# xio.net
KiCad netlist of a schematic drawn in EAGLE
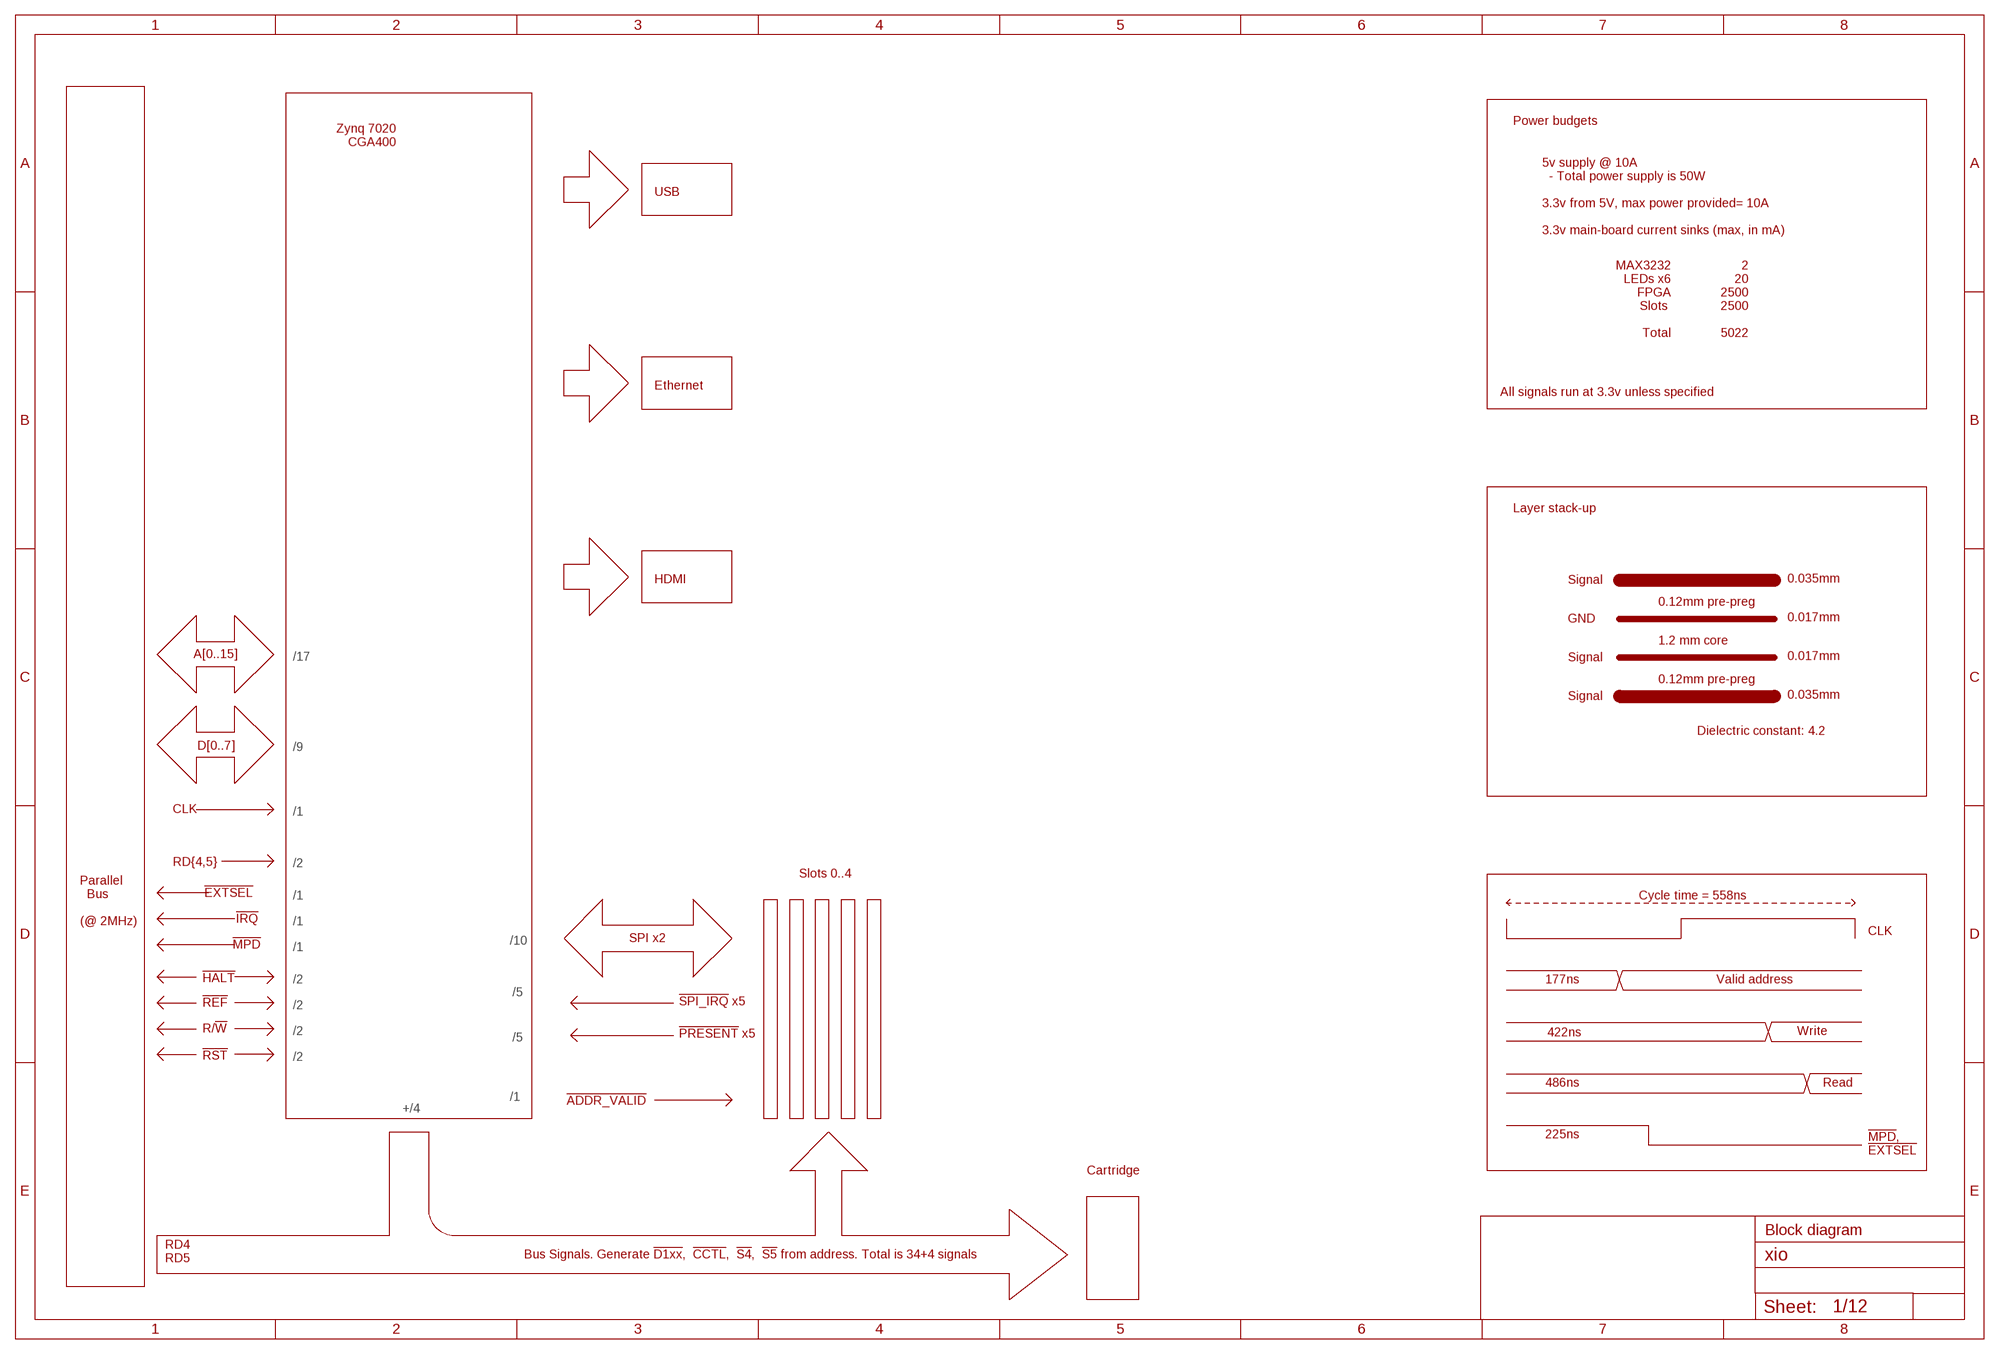
[diagram p0: schematic, sheet 1]
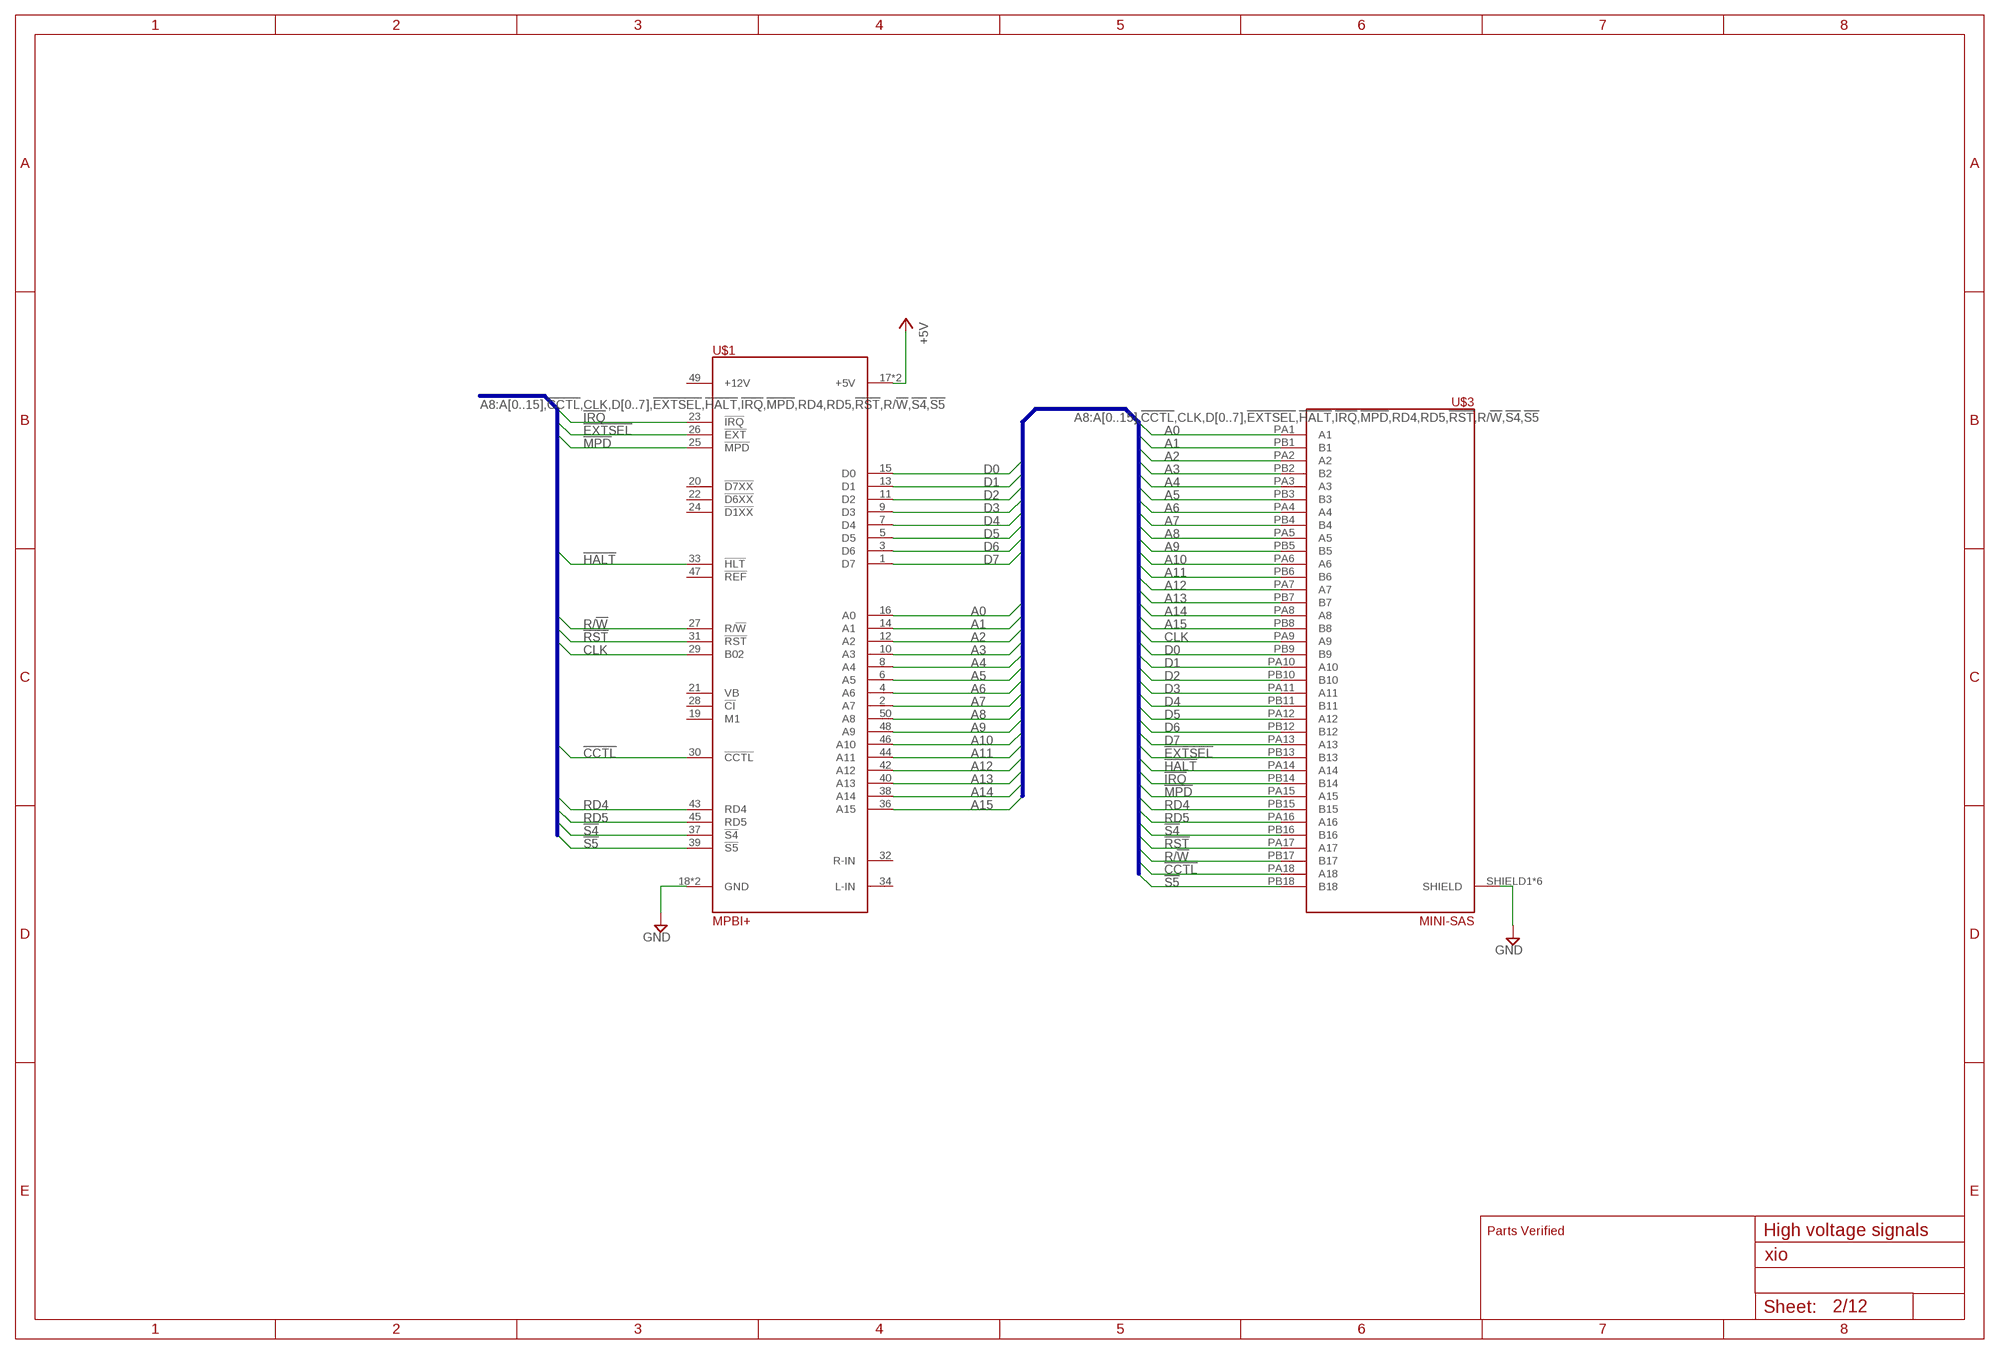
[diagram p1: schematic, sheet 2]
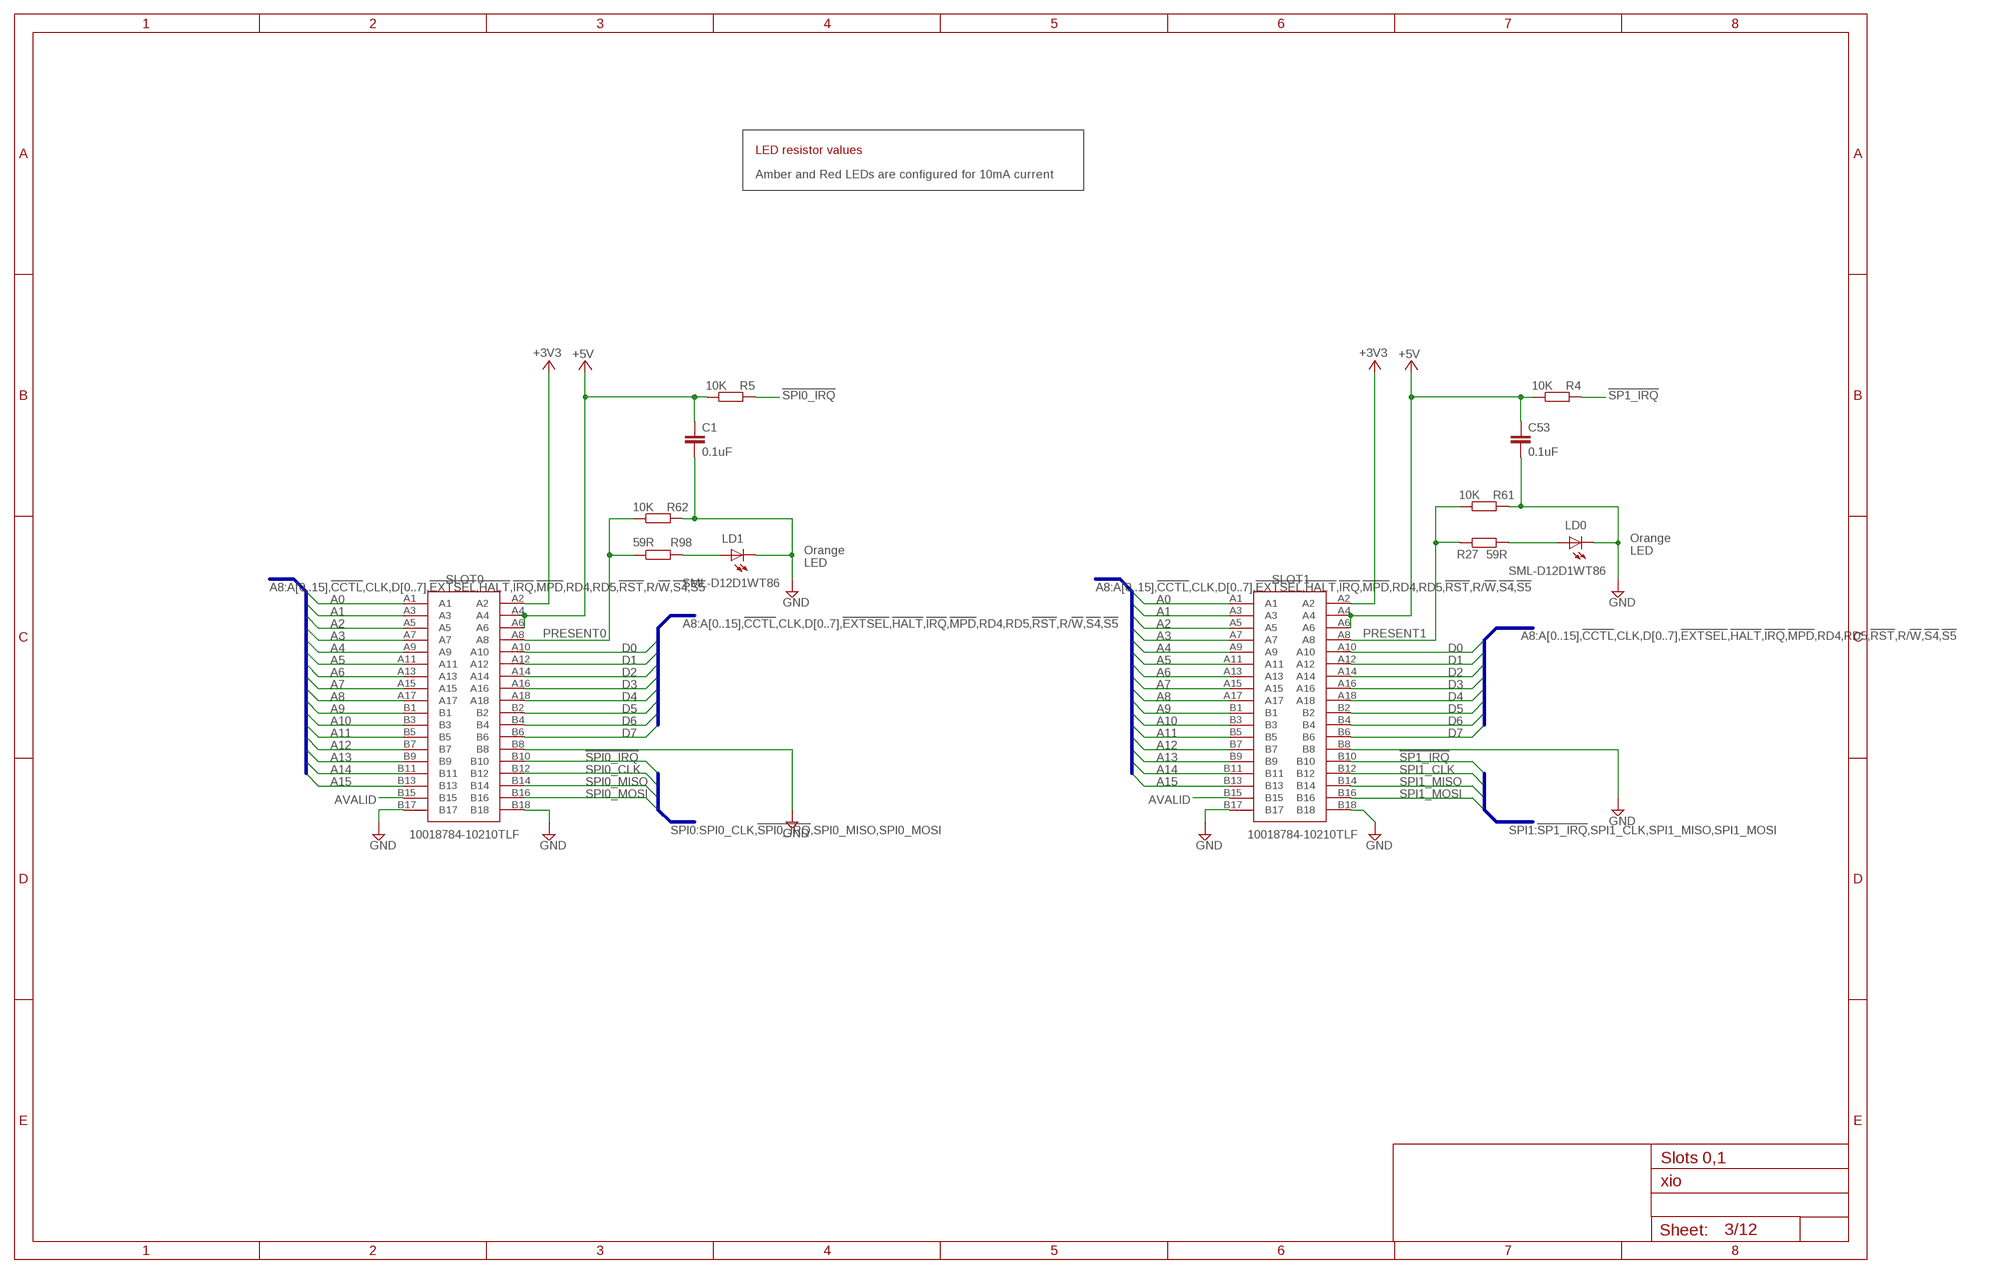
[diagram p2: schematic, sheet 3]
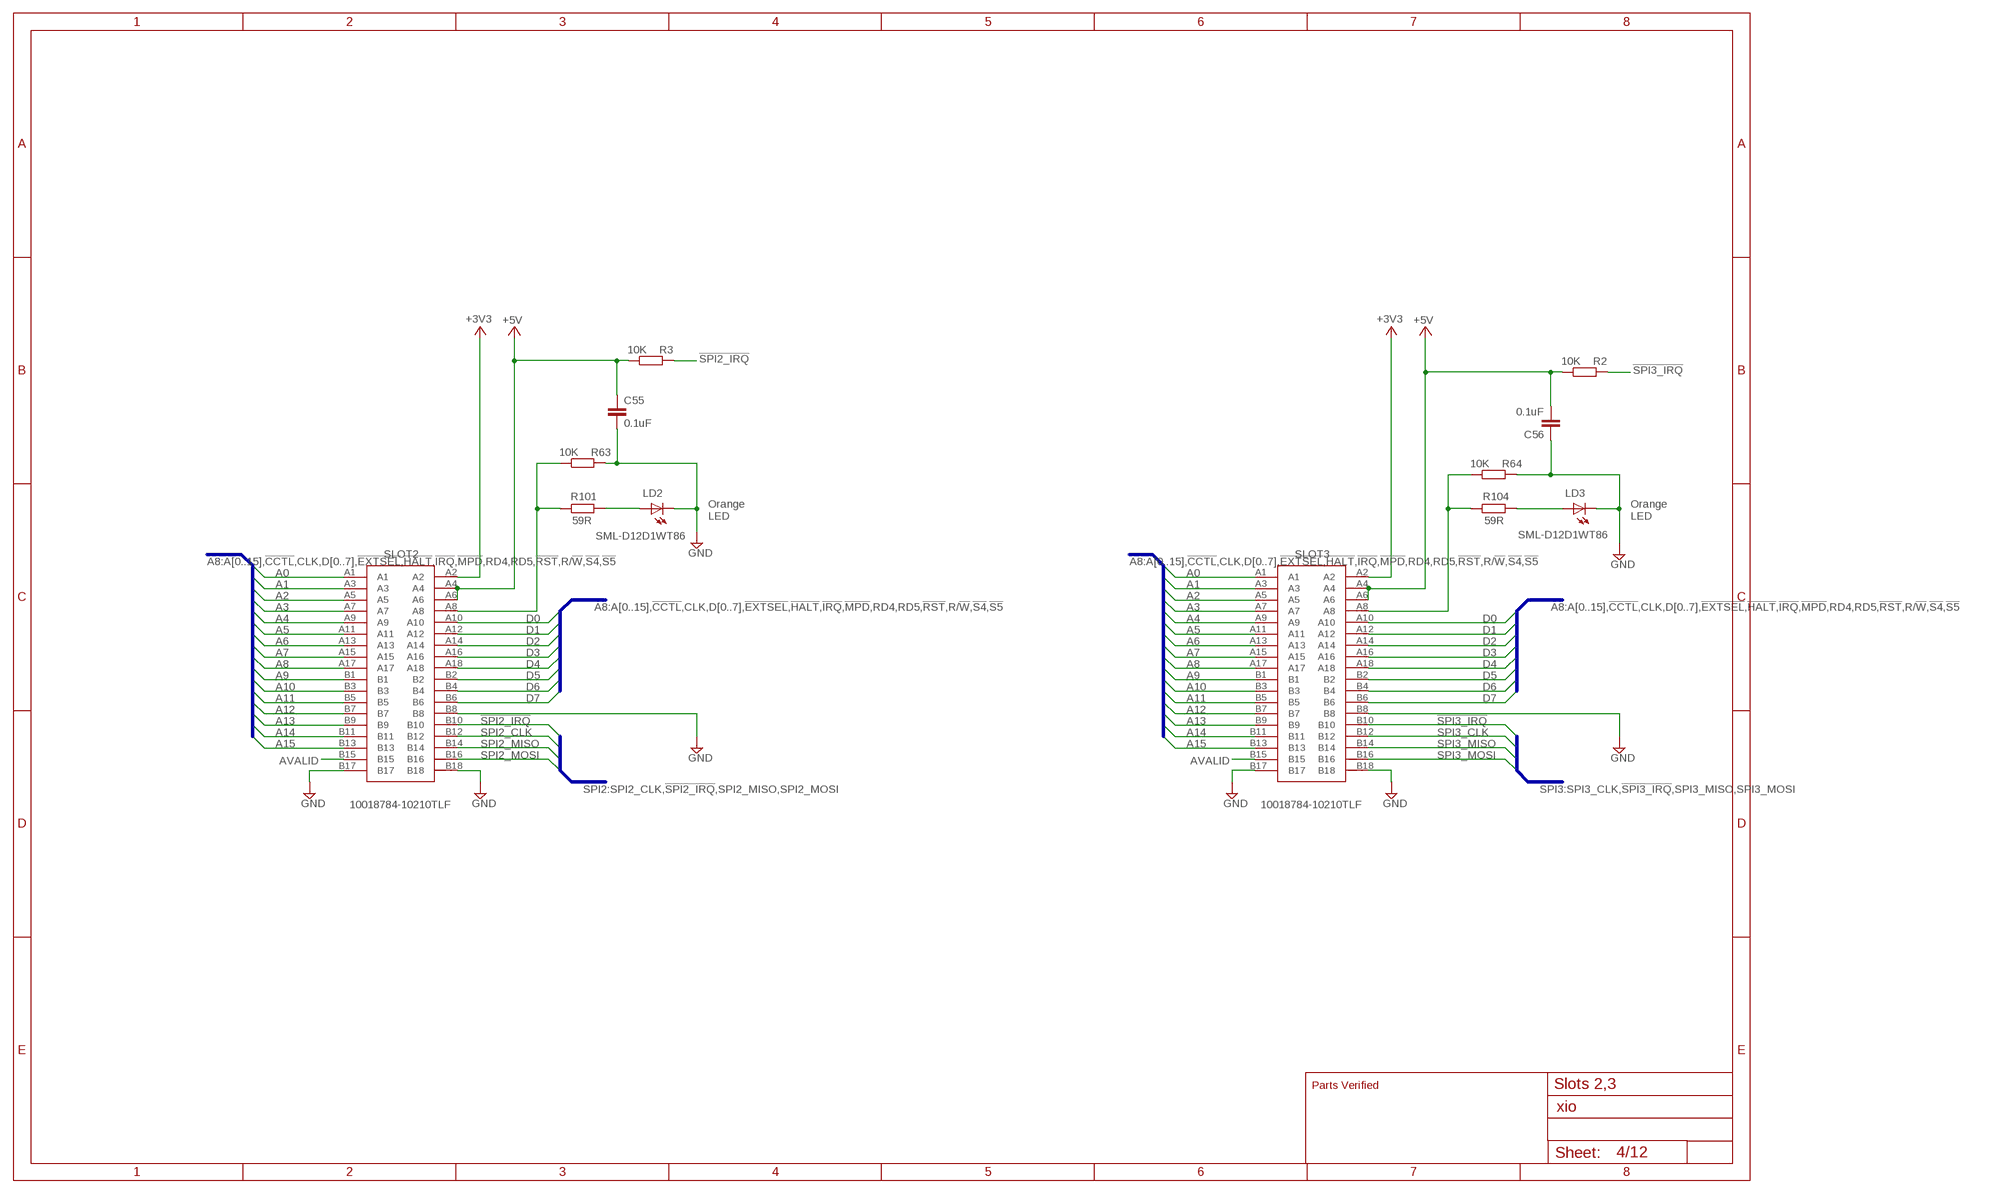
[diagram p3: schematic, sheet 4]
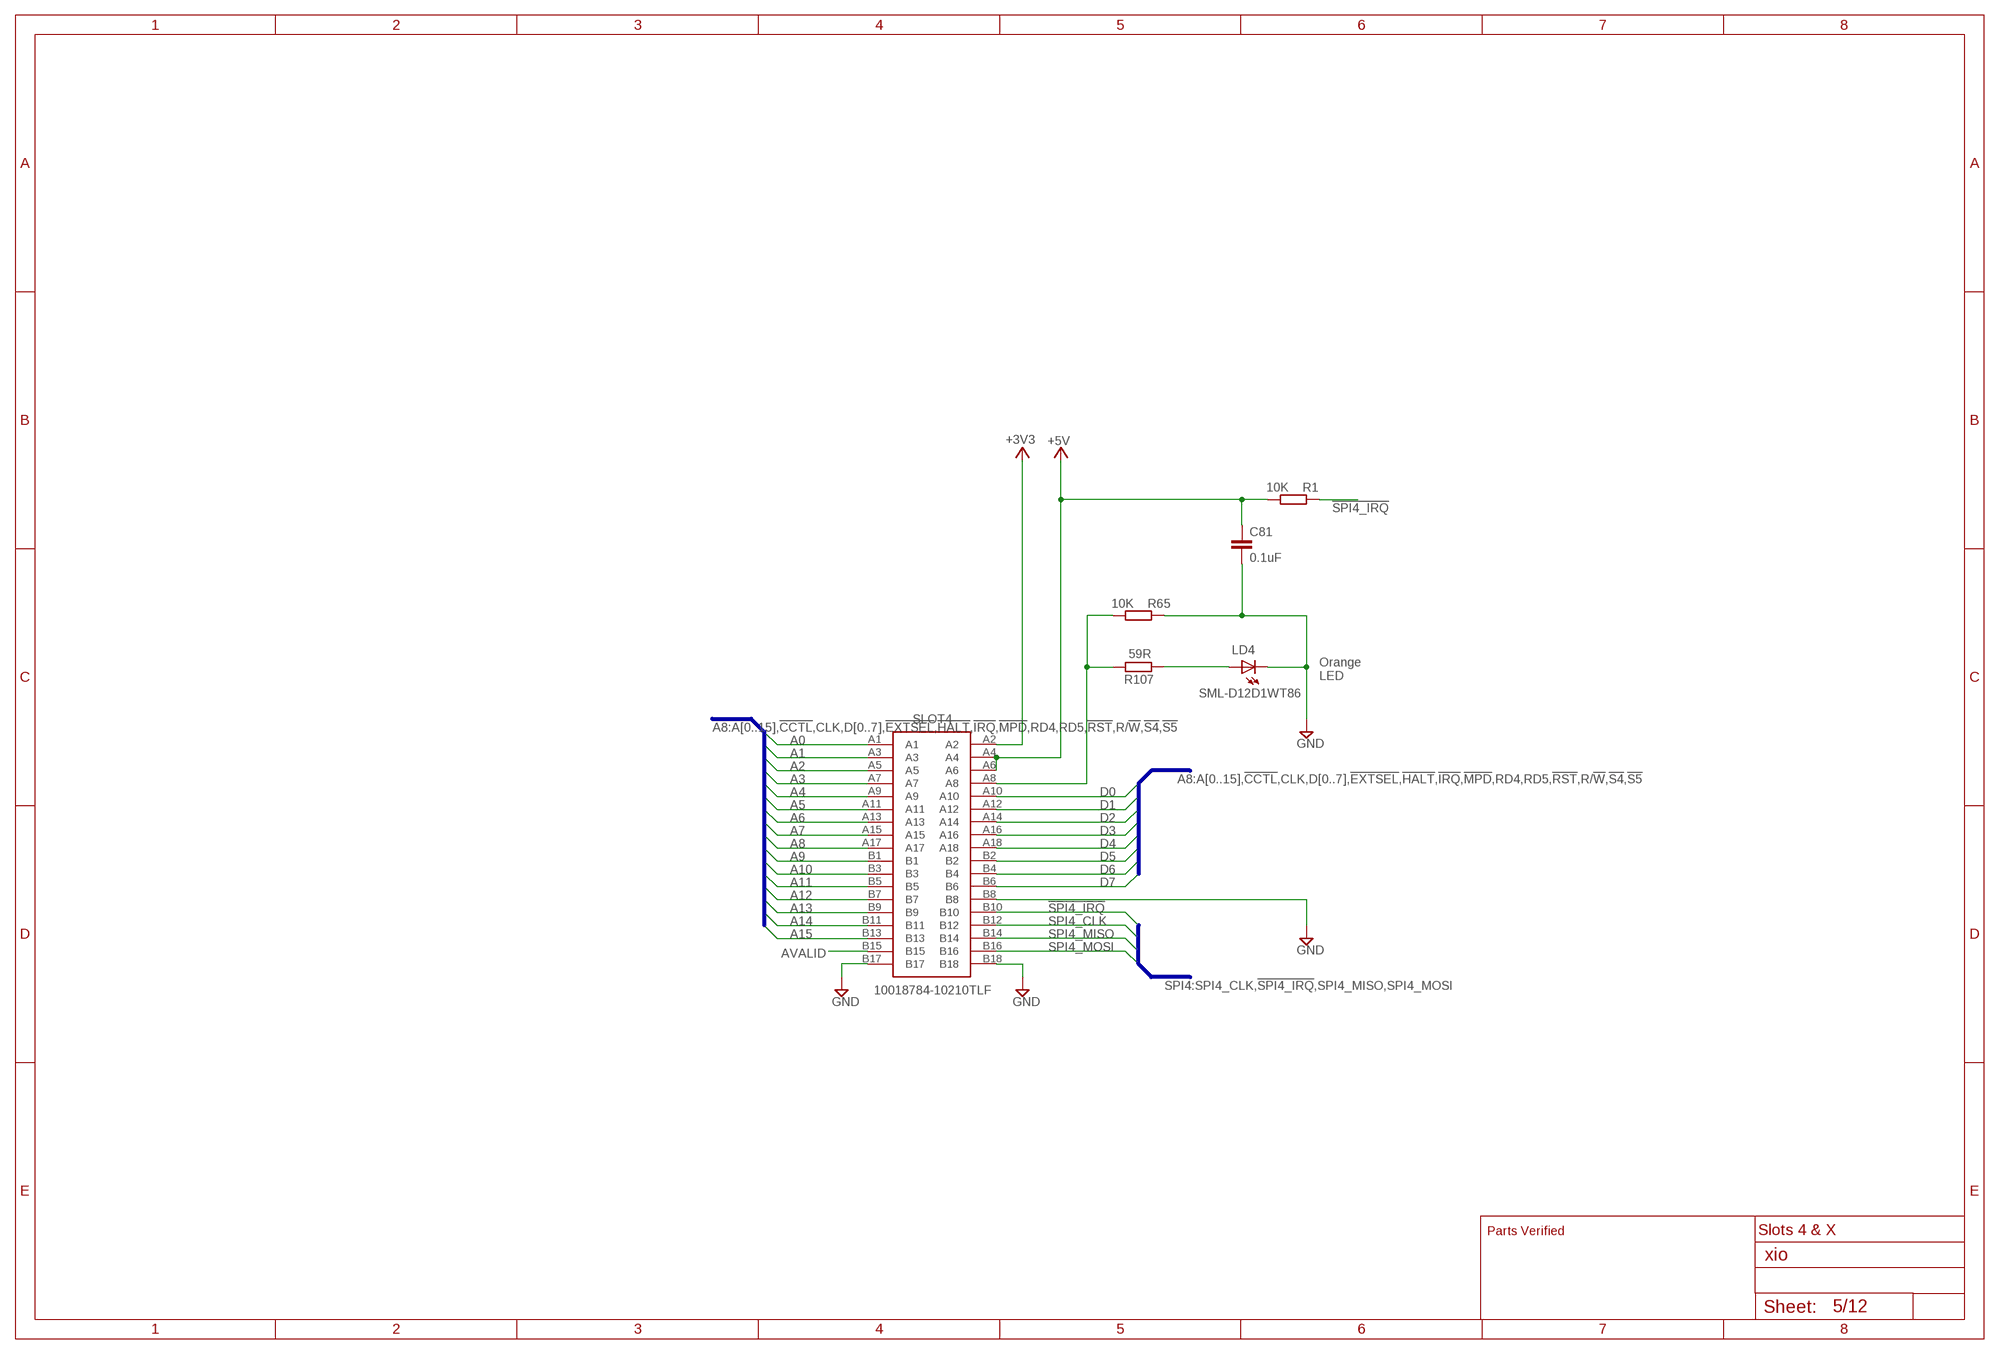
[diagram p4: schematic, sheet 5]
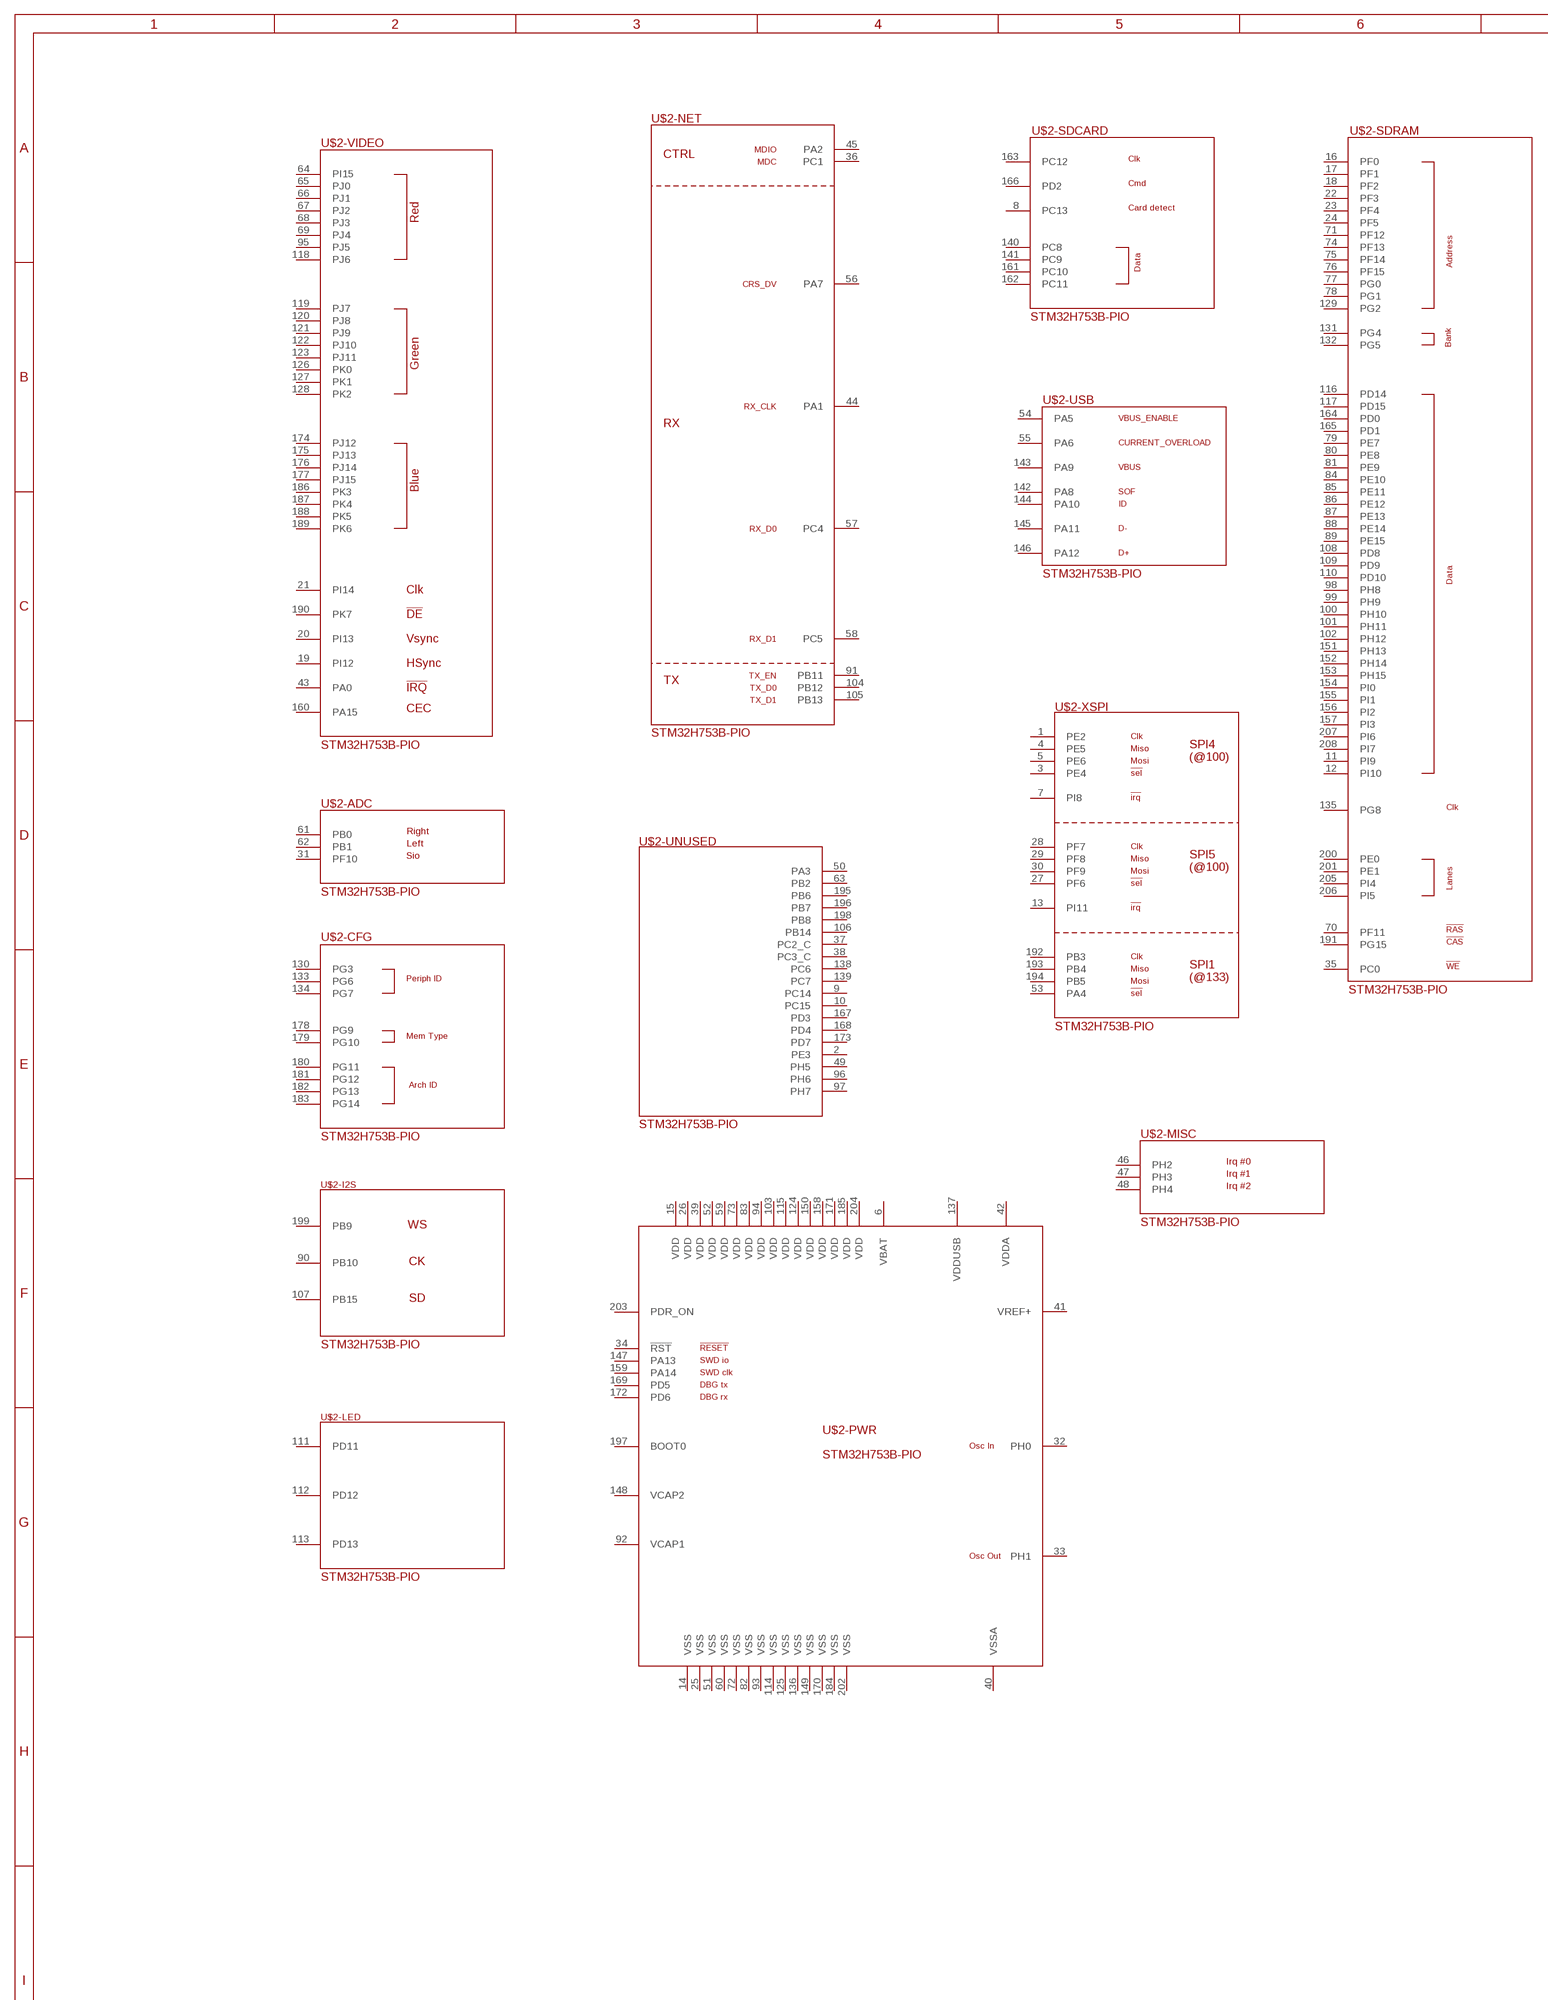
[diagram p5: schematic, sheet 6, part 1 of 2]
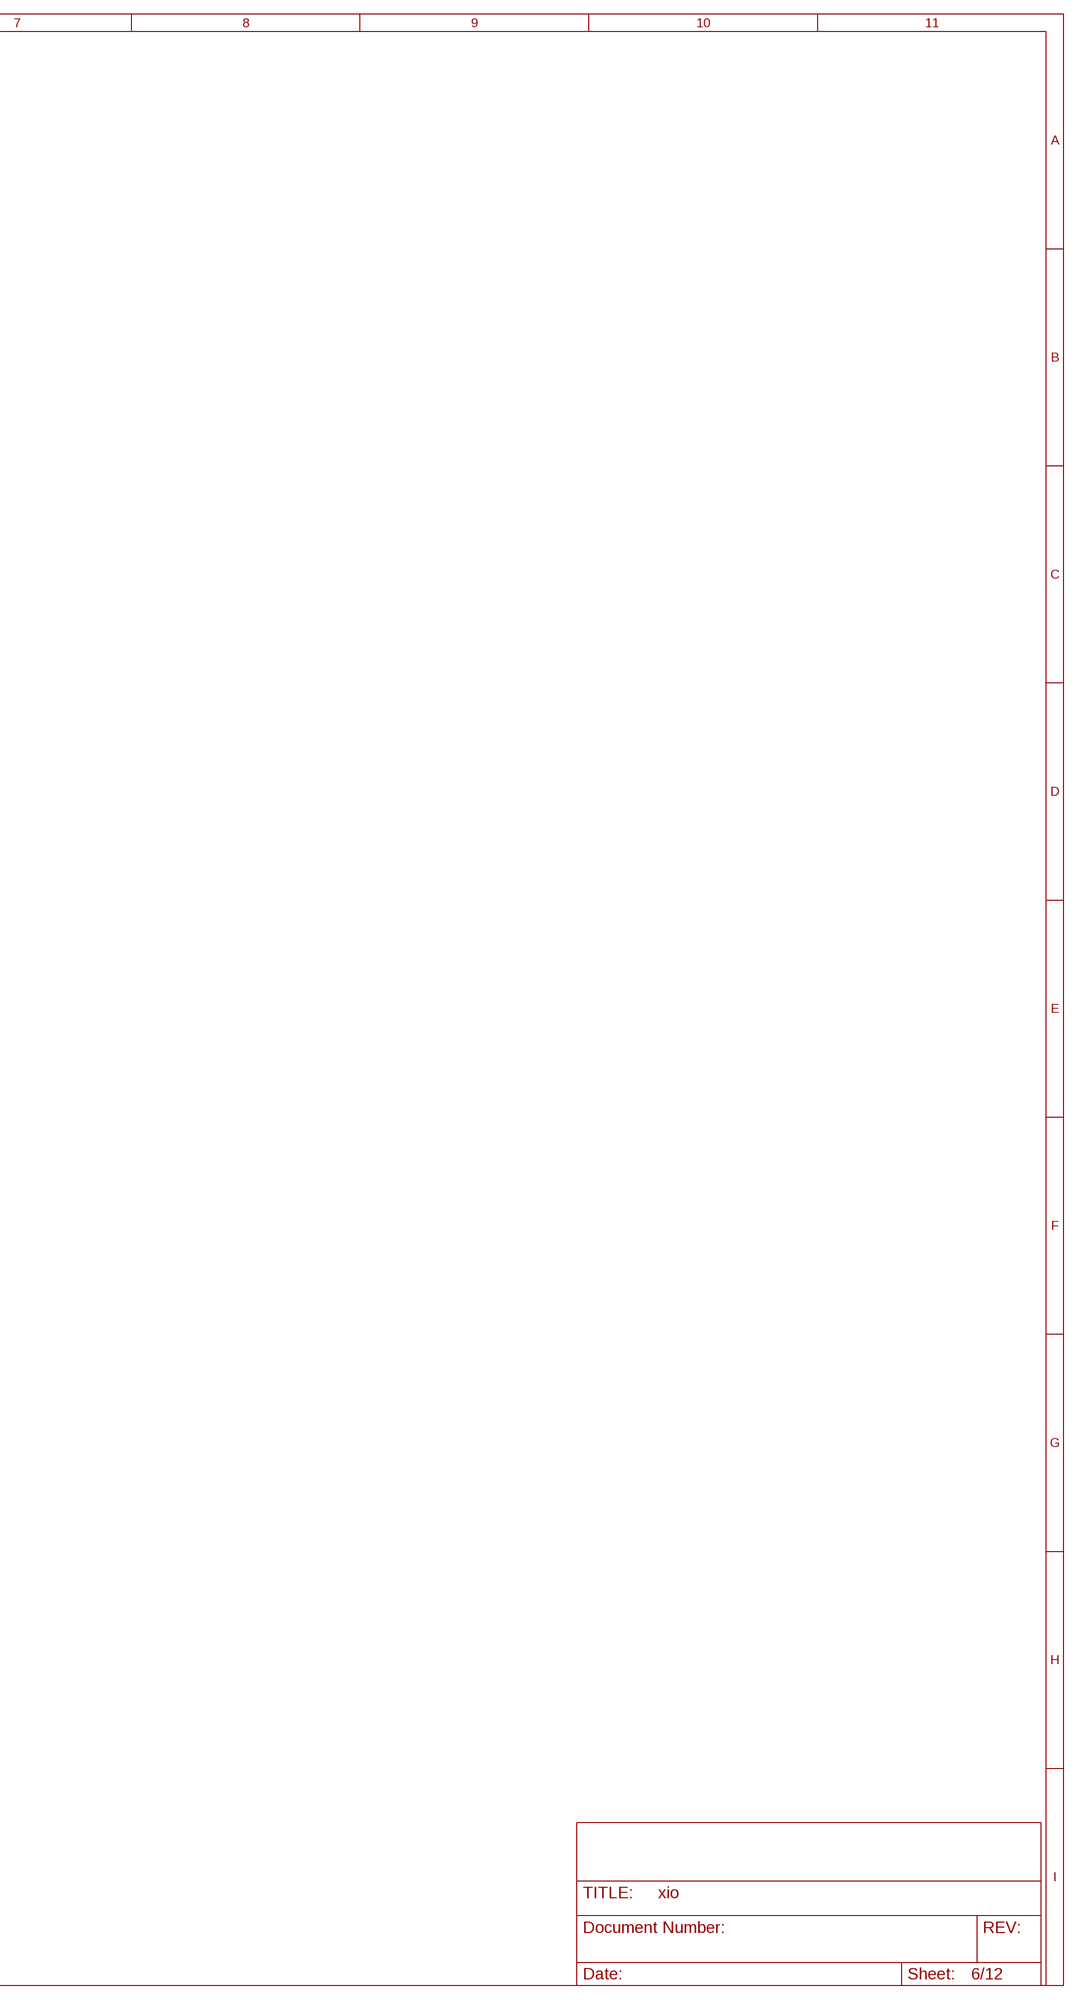
[diagram p6: schematic, sheet 6, part 2 of 2]
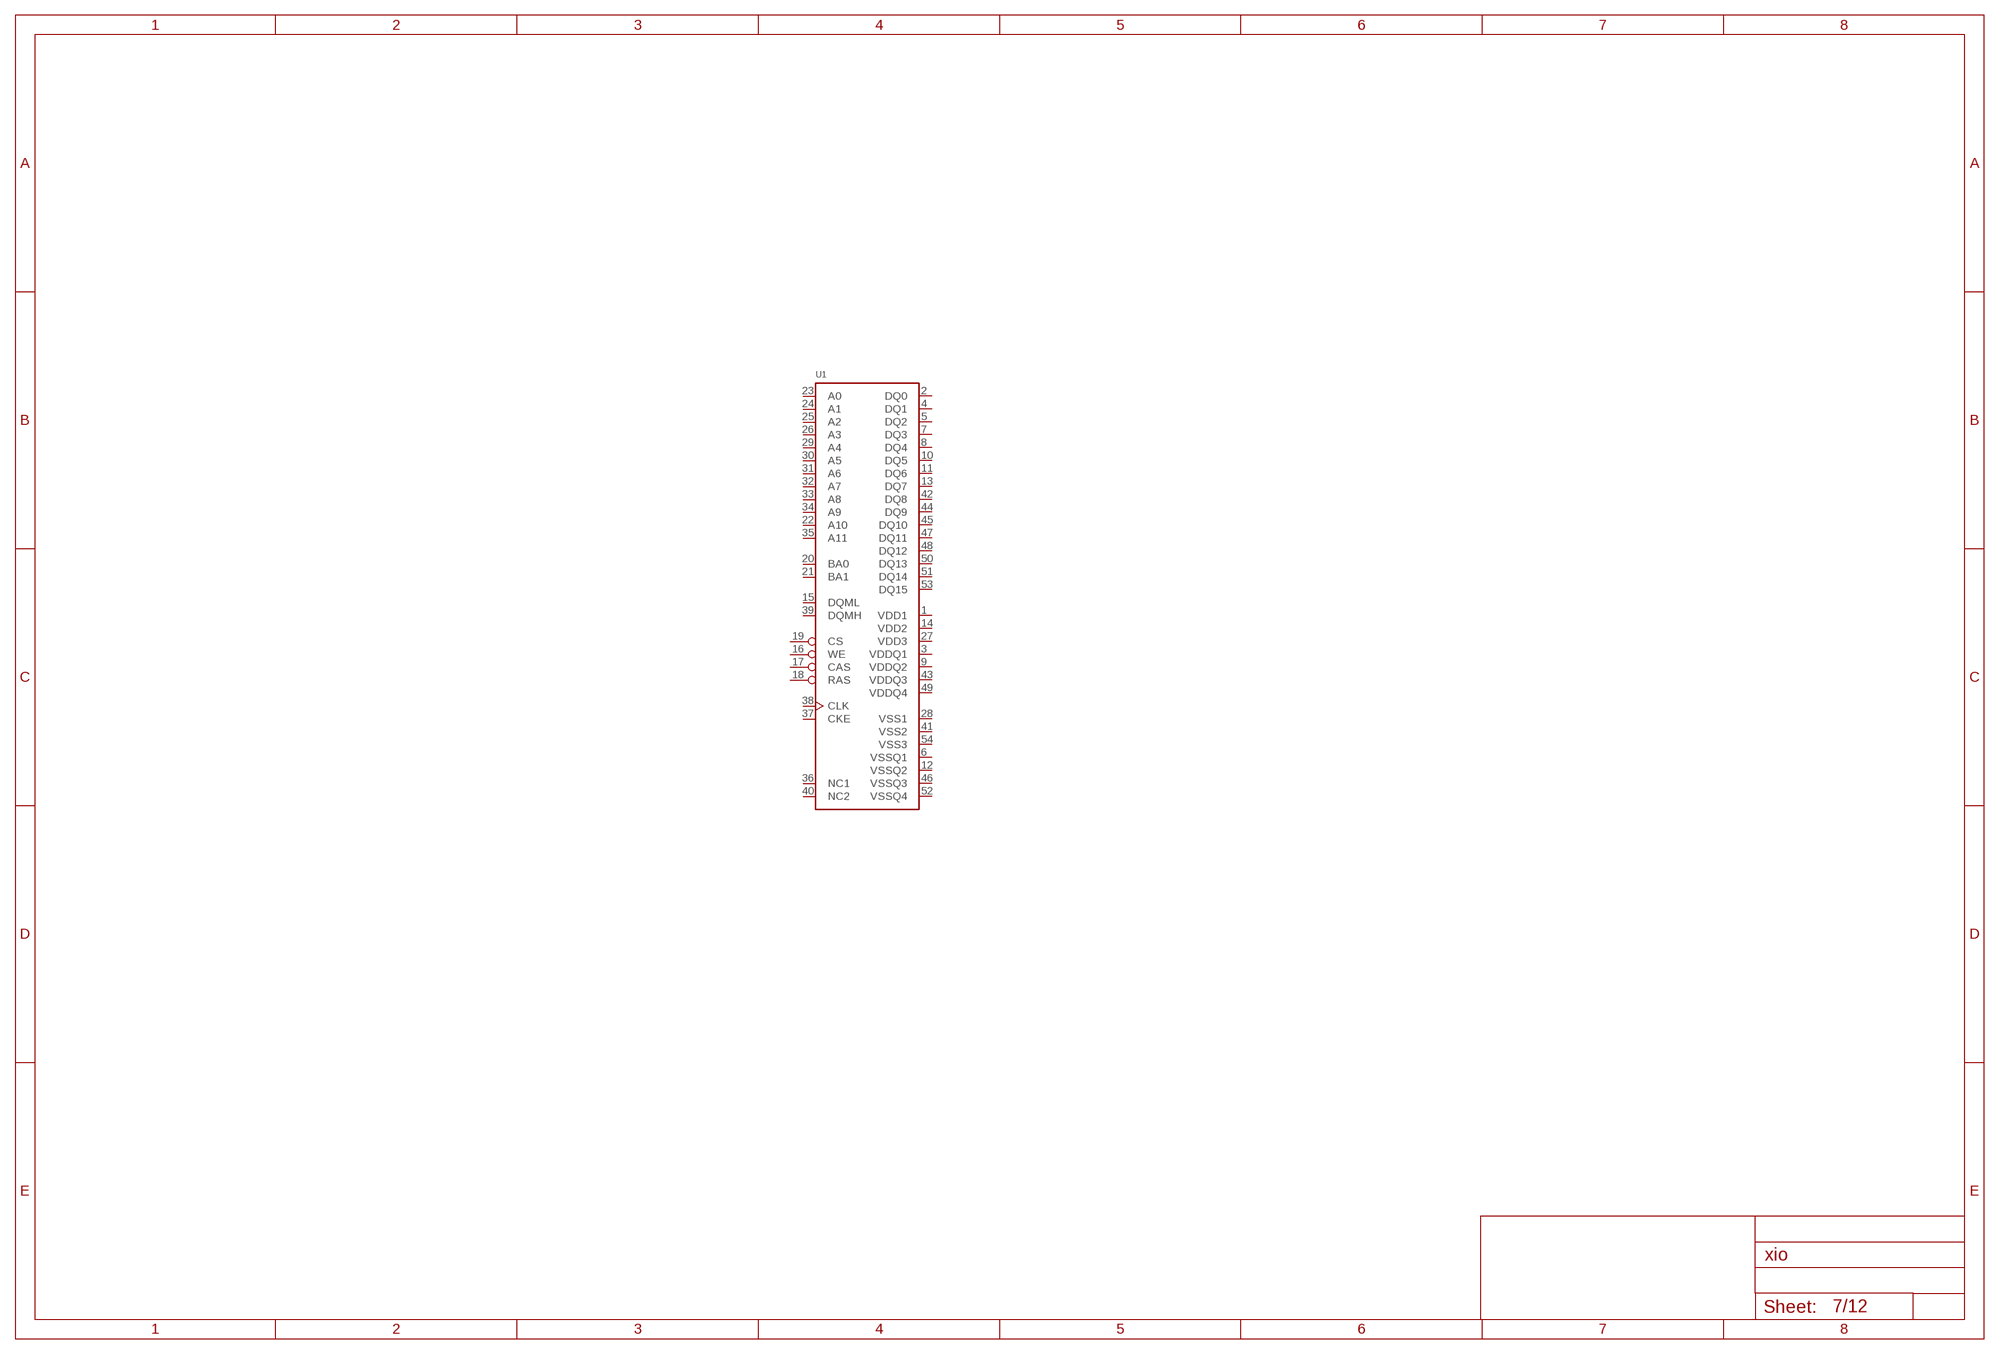
[diagram p7: schematic, sheet 7]
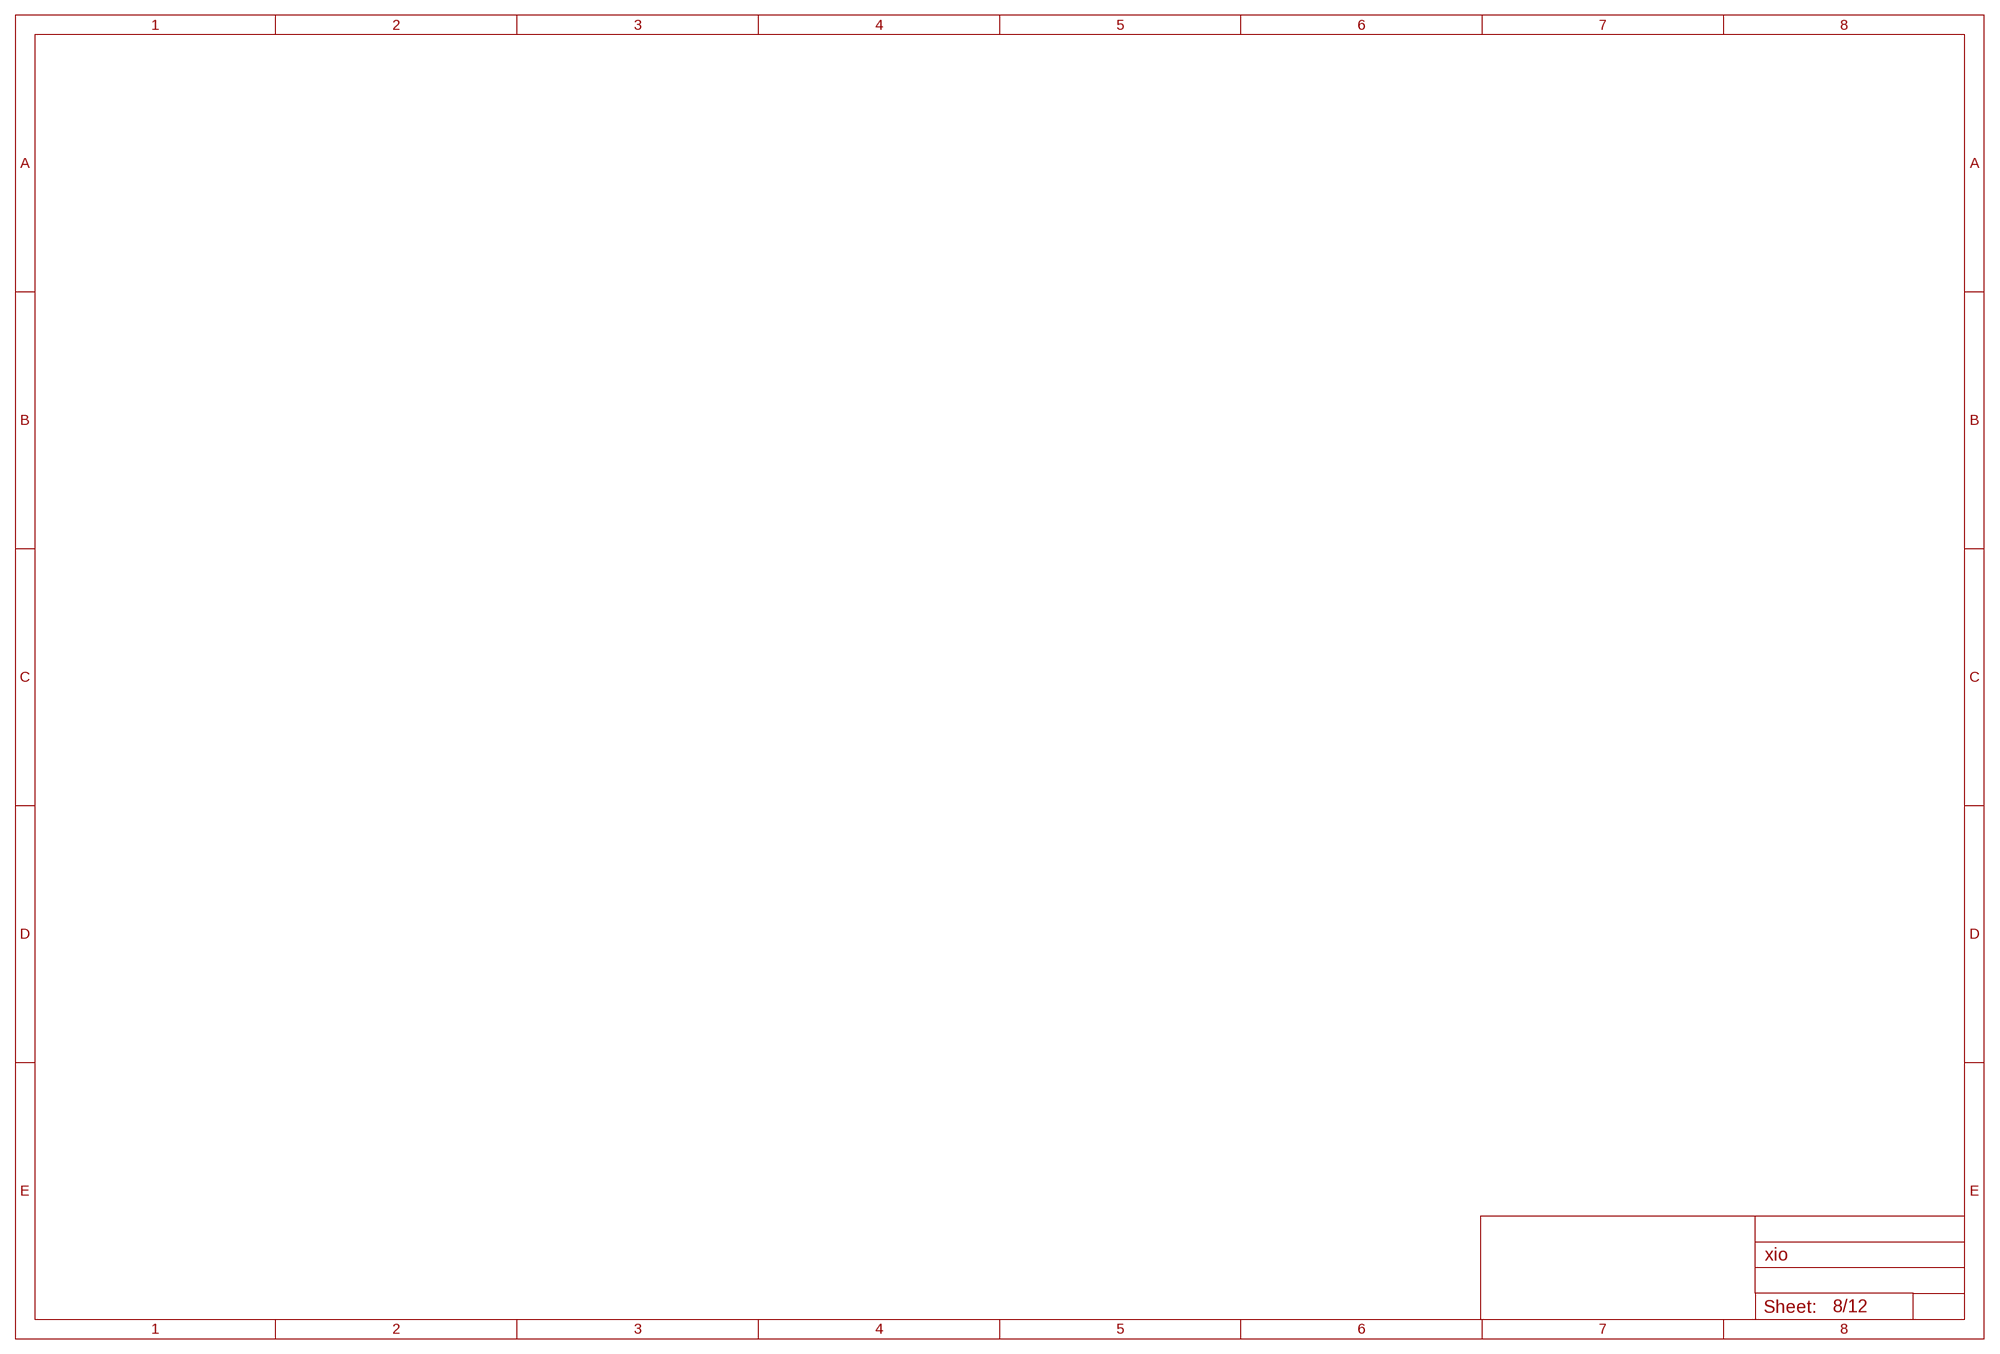
[diagram p8: schematic, sheet 8]
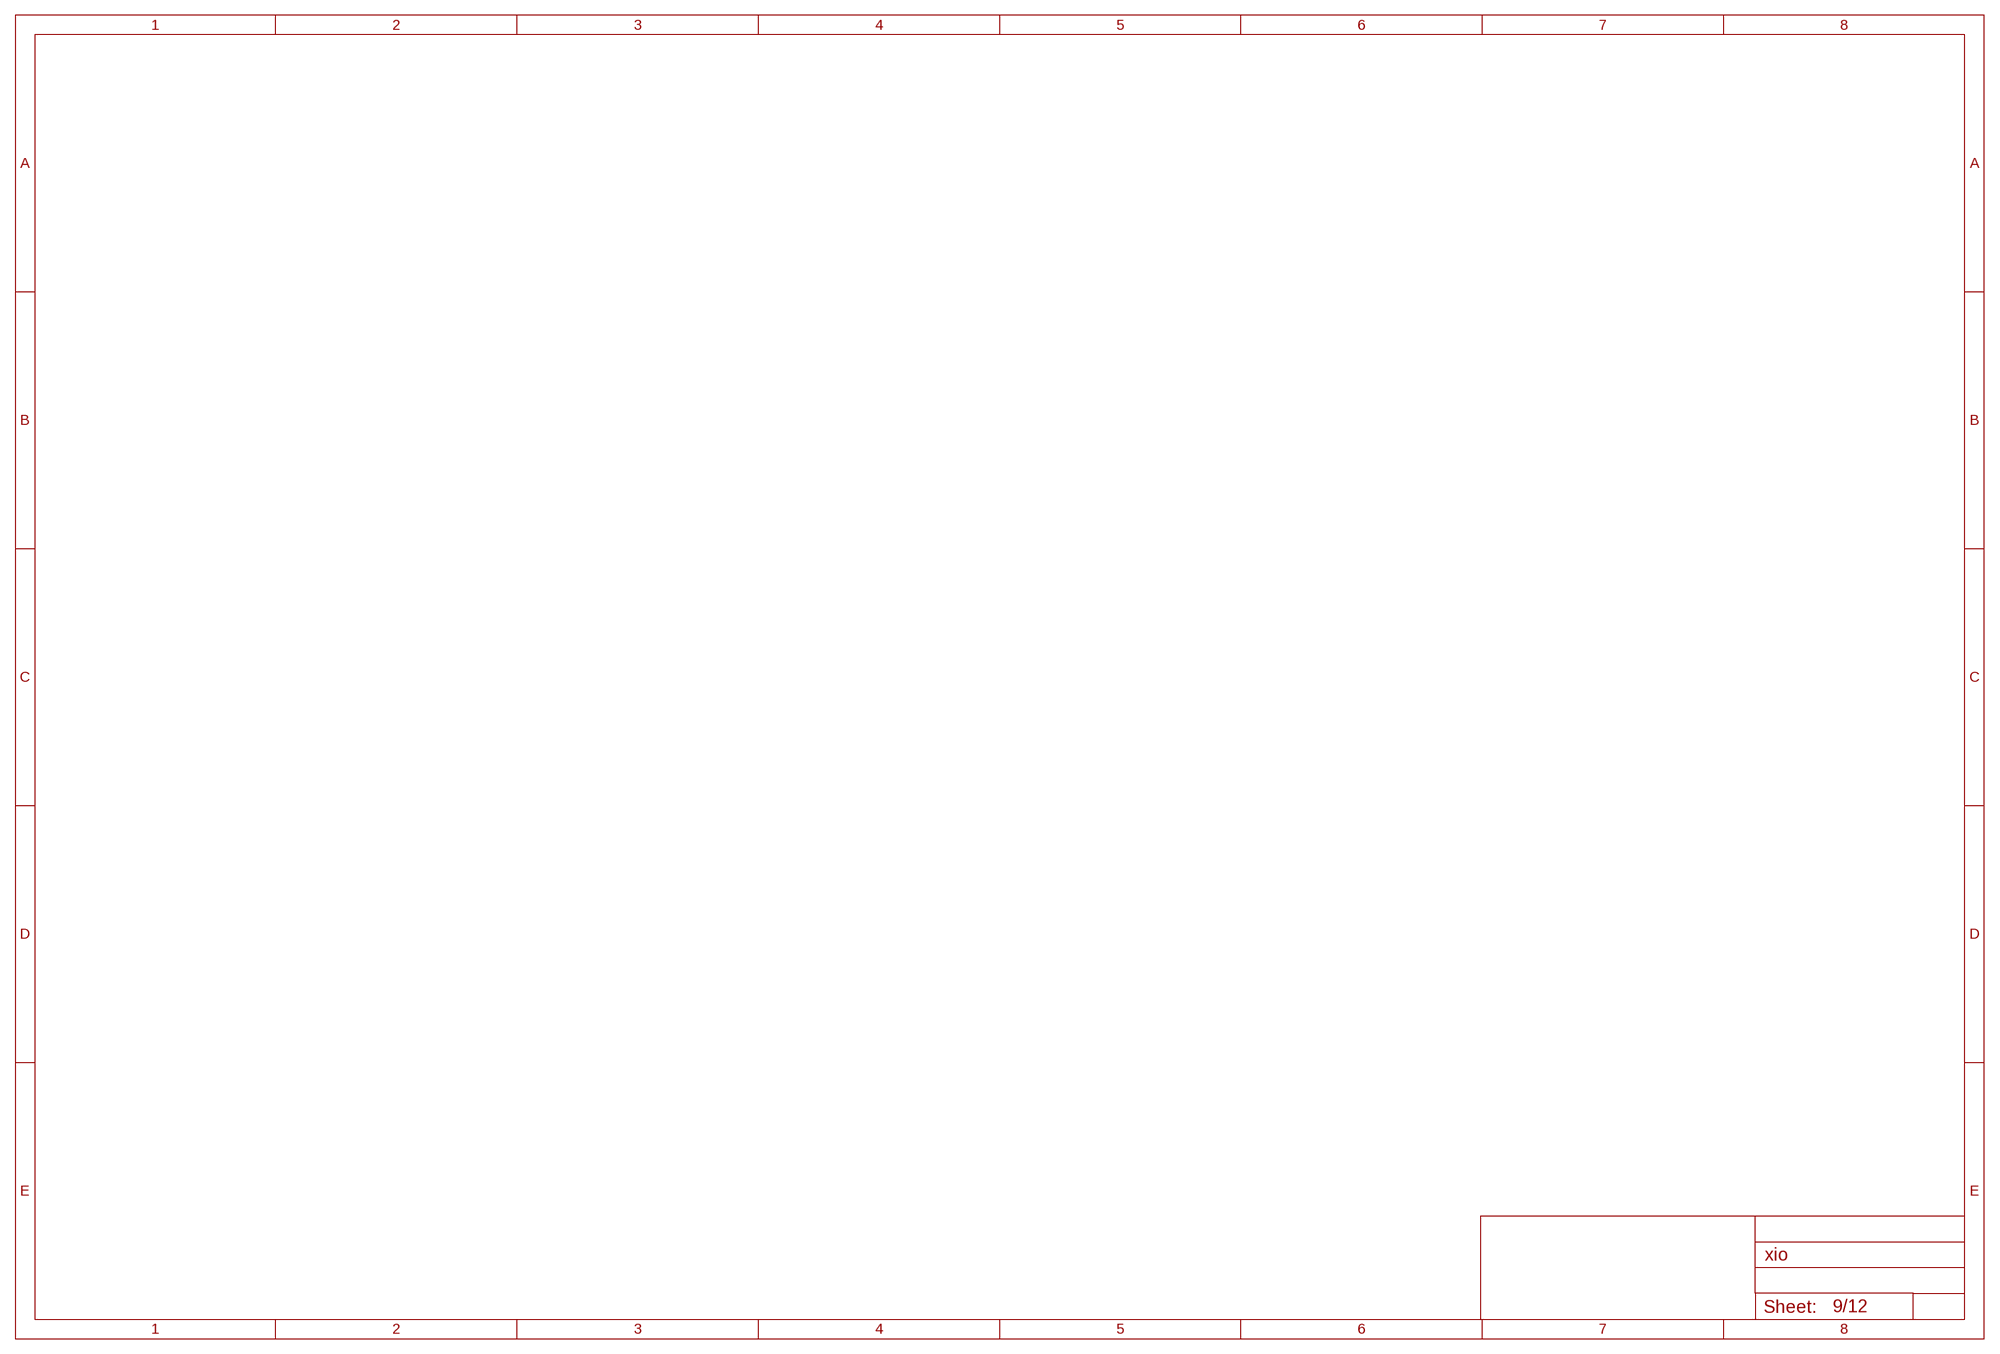
[diagram p9: schematic, sheet 9]
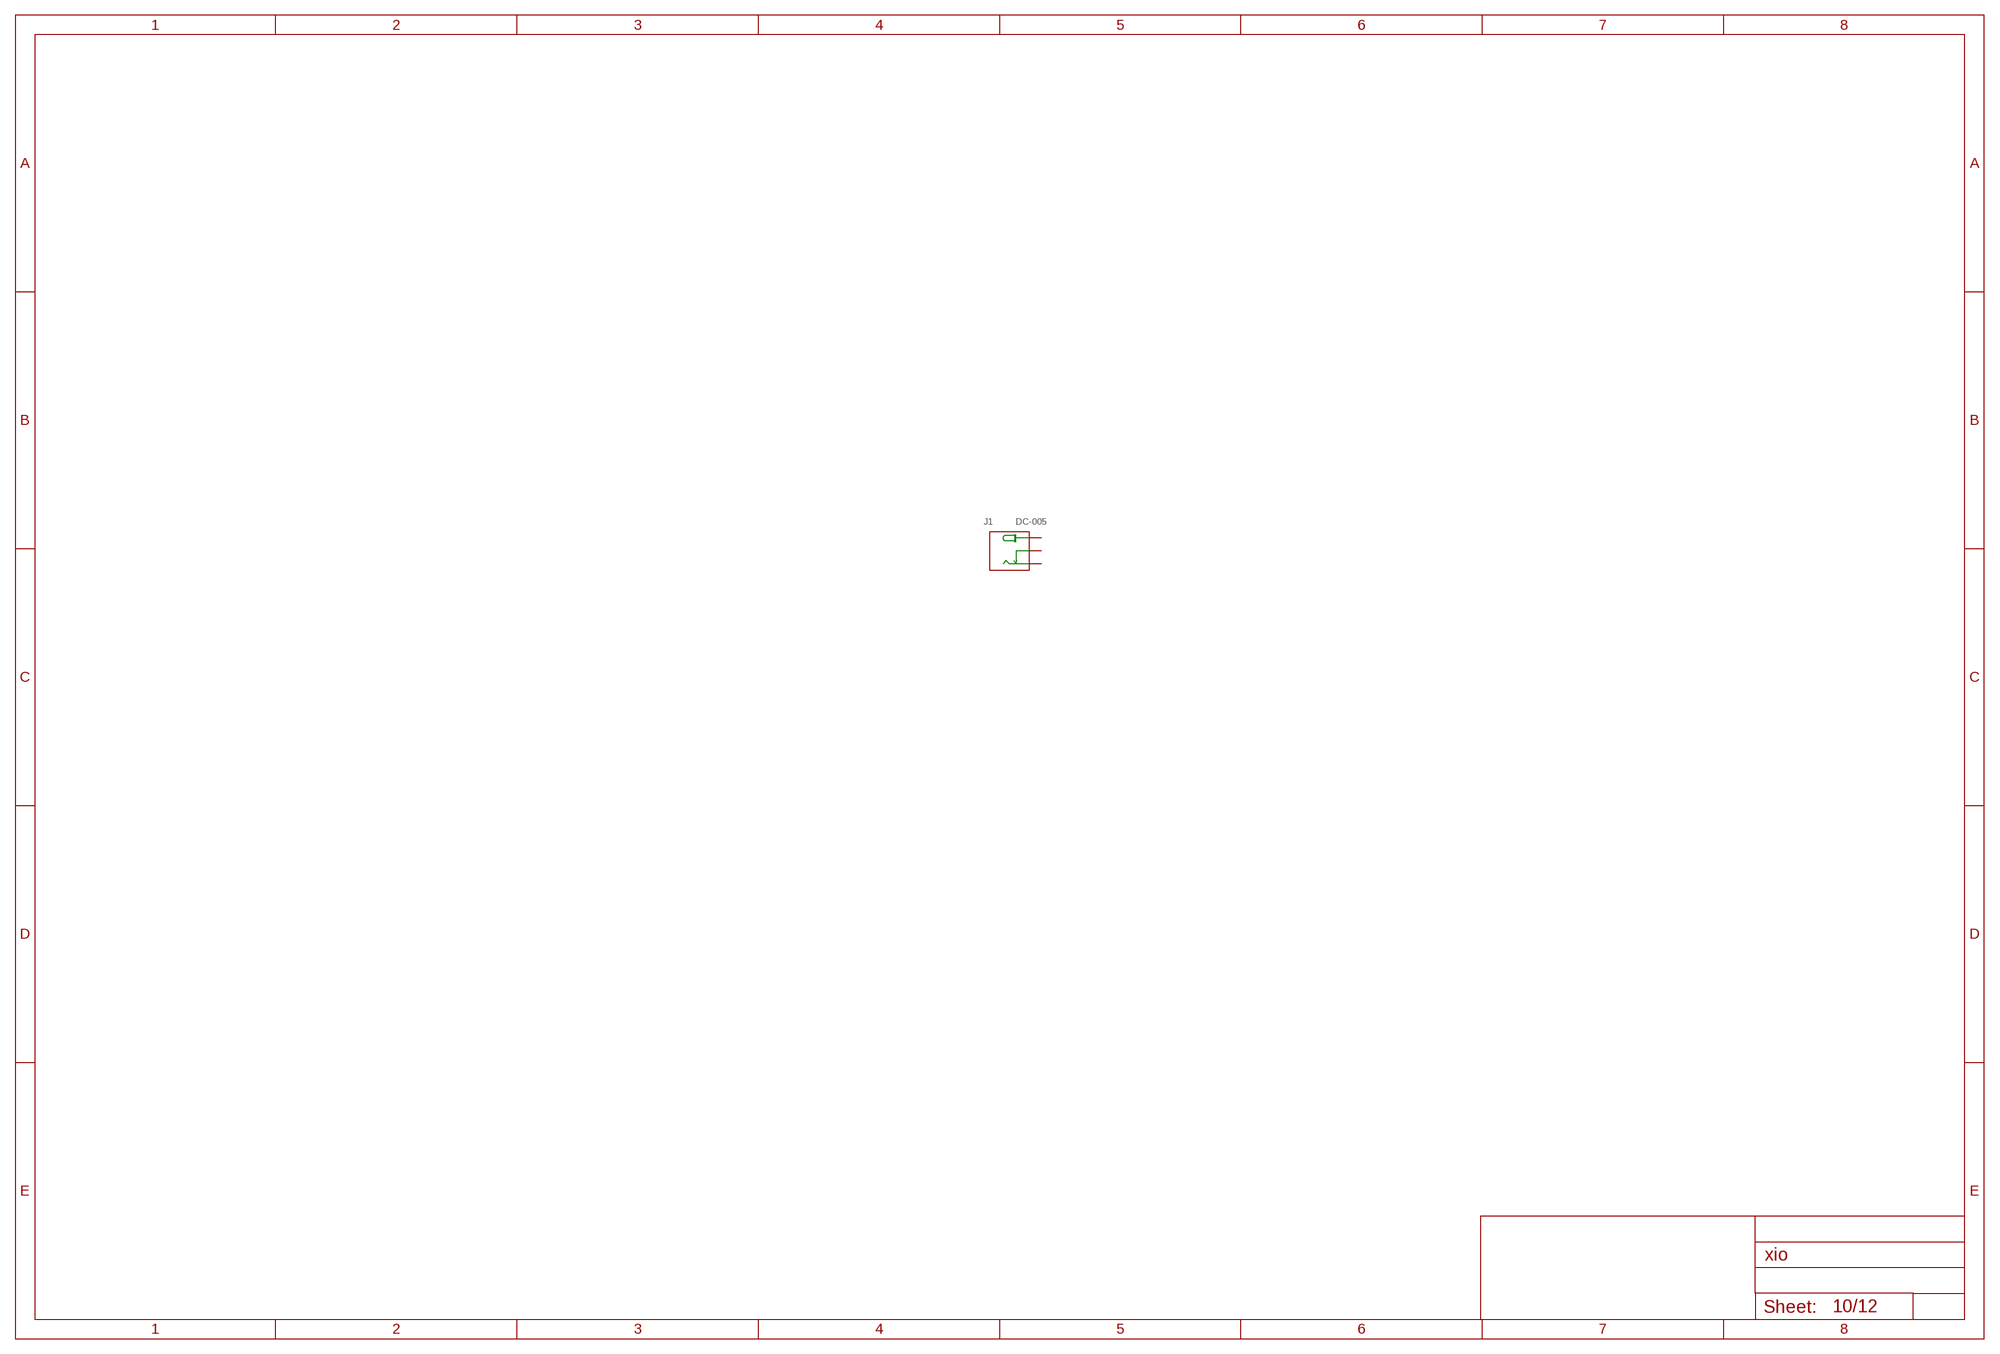
[diagram p10: schematic, sheet 10]
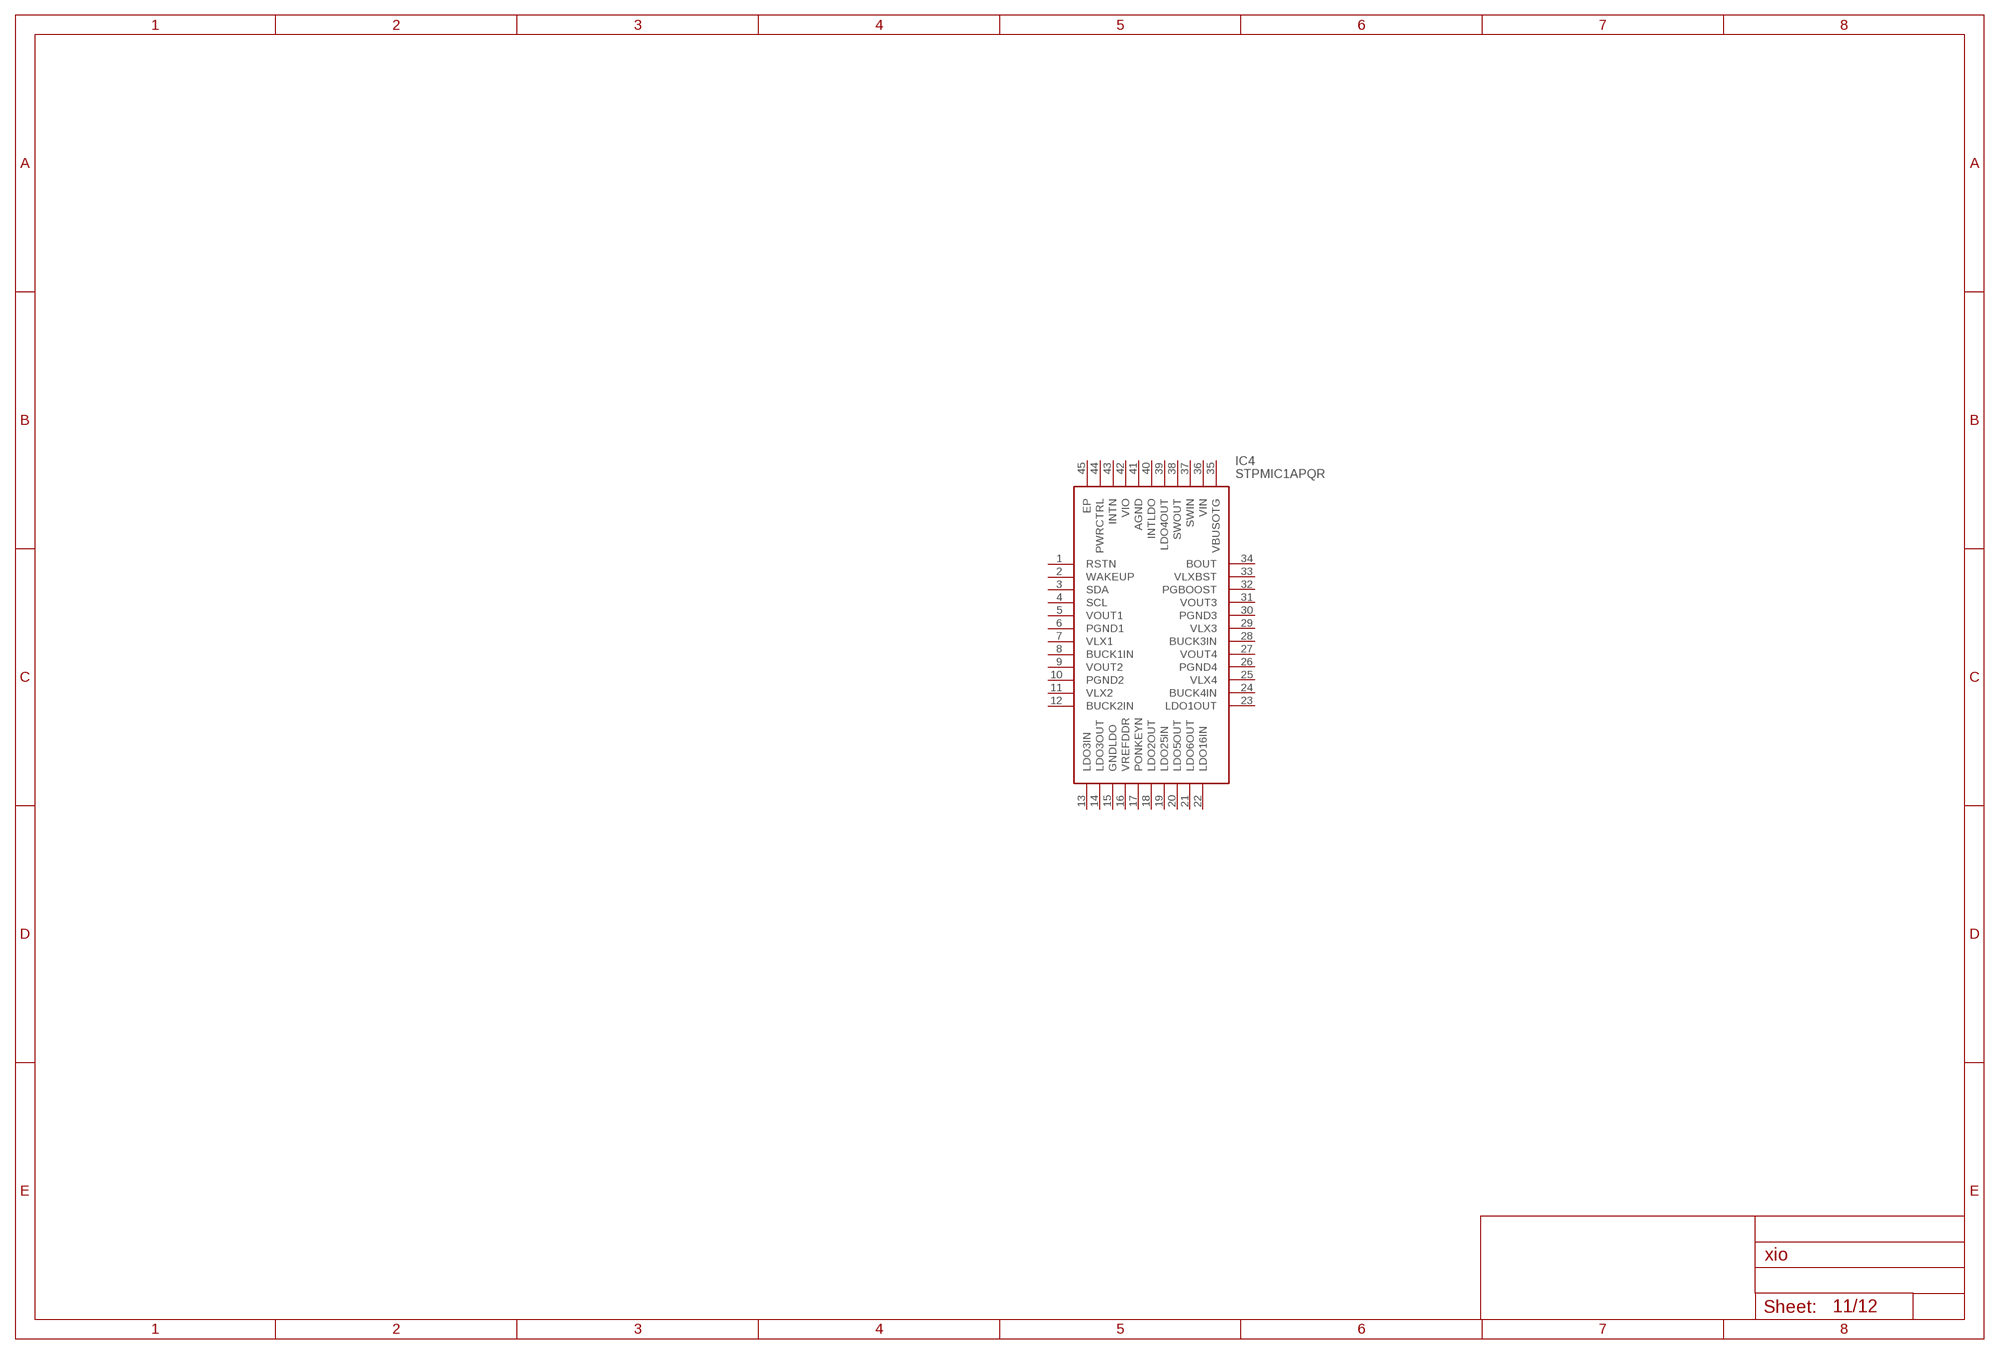
[diagram p11: schematic, sheet 11]

(export (version "E")
  (design (tool "Eeschema 10.0.6"))
  (components
    (comp (ref "C81")
      (value "0.1uF")
      (footprint "eagle-import:C0201")
      (libsource (lib "eagle-import") (part "C-EUC0201"))
    )
    (comp (ref "LD4")
      (value "SML-D12D1WT86")
      (footprint "eagle-import:CHIPLED_0603")
      (libsource (lib "eagle-import") (part "LEDCHIPLED_0603"))
    )
    (comp (ref "R1")
      (value "10K")
      (footprint "eagle-import:R0201")
      (libsource (lib "eagle-import") (part "R-EU_R0201"))
    )
    (comp (ref "R65")
      (value "10K")
      (footprint "eagle-import:R0201")
      (libsource (lib "eagle-import") (part "R-EU_R0201"))
    )
    (comp (ref "R107")
      (value "59R")
      (footprint "eagle-import:R0402")
      (libsource (lib "eagle-import") (part "R-EU_R0402"))
    )
    (comp (ref "SLOT4")
      (value "10018784-10210TLF")
      (footprint "eagle-import:1001878410210TLF")
      (fields (field (name "MOUSER_PART_NUMBER") "649-1001878410210TLF"))
      (libsource (lib "eagle-import") (part "10018784-10210TLF"))
    )
    (comp (ref "U1")
      (value "SDRAM_54TSOP")
      (footprint "eagle-import:TSOP54-400")
      (libsource (lib "eagle-import") (part "SDRAM_54TSOP"))
    )
    (comp (ref "U$2")
      (value "STM32H753B-PIO")
      (footprint "eagle-import:PQFP208")
      (fields (field (name "USE") "STM32H753BIT6"))
      (libsource (lib "eagle-import") (part "STM32H753B-PIO"))
    )
    (comp (ref "J1")
      (value "DC-005")
      (footprint "eagle-import:DCJ3P-14.2X11.0X9.0MM")
      (libsource (lib "eagle-import") (part "CONN-POWER-JACK-2.1MM(DC-005)"))
    )
    (comp (ref "IC4")
      (value "STPMIC1APQR")
      (footprint "eagle-import:QFN40P500X600X80-45N")
      (fields (field (name "MOUSER_PART_NUMBER") "511-STPMIC1APQR"))
      (libsource (lib "eagle-import") (part "STPMIC1APQR"))
    )
    (comp (ref "U$1")
      (value "MPBI+")
      (footprint "eagle-import:2X25")
      (libsource (lib "eagle-import") (part "MPBI+"))
    )
    (comp (ref "U$3")
      (value "MINI-SAS")
      (footprint "eagle-import:MINI-SAS")
      (libsource (lib "eagle-import") (part "MINI-SAS"))
    )
    (comp (ref "C1")
      (value "0.1uF")
      (footprint "eagle-import:C0201")
      (libsource (lib "eagle-import") (part "C-EUC0201"))
    )
    (comp (ref "C53")
      (value "0.1uF")
      (footprint "eagle-import:C0201")
      (libsource (lib "eagle-import") (part "C-EUC0201"))
    )
    (comp (ref "LD0")
      (value "SML-D12D1WT86")
      (footprint "eagle-import:CHIPLED_0603")
      (libsource (lib "eagle-import") (part "LEDCHIPLED_0603"))
    )
    (comp (ref "LD1")
      (value "SML-D12D1WT86")
      (footprint "eagle-import:CHIPLED_0603")
      (libsource (lib "eagle-import") (part "LEDCHIPLED_0603"))
    )
    (comp (ref "R4")
      (value "10K")
      (footprint "eagle-import:R0201")
      (libsource (lib "eagle-import") (part "R-EU_R0201"))
    )
    (comp (ref "R5")
      (value "10K")
      (footprint "eagle-import:R0201")
      (libsource (lib "eagle-import") (part "R-EU_R0201"))
    )
    (comp (ref "R27")
      (value "59R")
      (footprint "eagle-import:R0402")
      (libsource (lib "eagle-import") (part "R-EU_R0402"))
    )
    (comp (ref "R61")
      (value "10K")
      (footprint "eagle-import:R0201")
      (libsource (lib "eagle-import") (part "R-EU_R0201"))
    )
    (comp (ref "R62")
      (value "10K")
      (footprint "eagle-import:R0201")
      (libsource (lib "eagle-import") (part "R-EU_R0201"))
    )
    (comp (ref "R98")
      (value "59R")
      (footprint "eagle-import:R0402")
      (libsource (lib "eagle-import") (part "R-EU_R0402"))
    )
    (comp (ref "SLOT0")
      (value "10018784-10210TLF")
      (footprint "eagle-import:1001878410210TLF")
      (fields (field (name "MOUSER_PART_NUMBER") "649-1001878410210TLF"))
      (libsource (lib "eagle-import") (part "10018784-10210TLF"))
    )
    (comp (ref "SLOT1")
      (value "10018784-10210TLF")
      (footprint "eagle-import:1001878410210TLF")
      (fields (field (name "MOUSER_PART_NUMBER") "649-1001878410210TLF"))
      (libsource (lib "eagle-import") (part "10018784-10210TLF"))
    )
    (comp (ref "C55")
      (value "0.1uF")
      (footprint "eagle-import:C0201")
      (libsource (lib "eagle-import") (part "C-EUC0201"))
    )
    (comp (ref "C56")
      (value "0.1uF")
      (footprint "eagle-import:C0201")
      (libsource (lib "eagle-import") (part "C-EUC0201"))
    )
    (comp (ref "LD2")
      (value "SML-D12D1WT86")
      (footprint "eagle-import:CHIPLED_0603")
      (libsource (lib "eagle-import") (part "LEDCHIPLED_0603"))
    )
    (comp (ref "LD3")
      (value "SML-D12D1WT86")
      (footprint "eagle-import:CHIPLED_0603")
      (libsource (lib "eagle-import") (part "LEDCHIPLED_0603"))
    )
    (comp (ref "R2")
      (value "10K")
      (footprint "eagle-import:R0201")
      (libsource (lib "eagle-import") (part "R-EU_R0201"))
    )
    (comp (ref "R3")
      (value "10K")
      (footprint "eagle-import:R0201")
      (libsource (lib "eagle-import") (part "R-EU_R0201"))
    )
    (comp (ref "R63")
      (value "10K")
      (footprint "eagle-import:R0201")
      (libsource (lib "eagle-import") (part "R-EU_R0201"))
    )
    (comp (ref "R64")
      (value "10K")
      (footprint "eagle-import:R0201")
      (libsource (lib "eagle-import") (part "R-EU_R0201"))
    )
    (comp (ref "R101")
      (value "59R")
      (footprint "eagle-import:R0402")
      (libsource (lib "eagle-import") (part "R-EU_R0402"))
    )
    (comp (ref "R104")
      (value "59R")
      (footprint "eagle-import:R0402")
      (libsource (lib "eagle-import") (part "R-EU_R0402"))
    )
    (comp (ref "SLOT2")
      (value "10018784-10210TLF")
      (footprint "eagle-import:1001878410210TLF")
      (fields (field (name "MOUSER_PART_NUMBER") "649-1001878410210TLF"))
      (libsource (lib "eagle-import") (part "10018784-10210TLF"))
    )
    (comp (ref "SLOT3")
      (value "10018784-10210TLF")
      (footprint "eagle-import:1001878410210TLF")
      (fields (field (name "MOUSER_PART_NUMBER") "649-1001878410210TLF"))
      (libsource (lib "eagle-import") (part "10018784-10210TLF"))
    )
  )
  (nets
    (net (code "42") (name "+3V3") (class "Default")
      (node (ref "SLOT0") (pin "A2") (pinfunction "A2_A2") (pintype "bidirectional"))
      (node (ref "SLOT1") (pin "A2") (pinfunction "A2_A2") (pintype "bidirectional"))
      (node (ref "SLOT2") (pin "A2") (pinfunction "A2_A2") (pintype "bidirectional"))
      (node (ref "SLOT3") (pin "A2") (pinfunction "A2_A2") (pintype "bidirectional"))
      (node (ref "SLOT4") (pin "A2") (pinfunction "A2_A2") (pintype "bidirectional"))
    )
    (net (code "43") (name "+5V") (class "Default")
      (node (ref "C1") (pin "1") (pinfunction "1_1") (pintype "passive"))
      (node (ref "C53") (pin "1") (pinfunction "1_1") (pintype "passive"))
      (node (ref "C55") (pin "1") (pinfunction "1_1") (pintype "passive"))
      (node (ref "C56") (pin "2") (pinfunction "2_2") (pintype "passive"))
      (node (ref "C81") (pin "1") (pinfunction "1_1") (pintype "passive"))
      (node (ref "R1") (pin "1") (pinfunction "1_1") (pintype "passive"))
      (node (ref "R2") (pin "1") (pinfunction "1_1") (pintype "passive"))
      (node (ref "R3") (pin "1") (pinfunction "1_1") (pintype "passive"))
      (node (ref "R4") (pin "1") (pinfunction "1_1") (pintype "passive"))
      (node (ref "R5") (pin "1") (pinfunction "1_1") (pintype "passive"))
      (node (ref "SLOT0") (pin "A4") (pinfunction "A4_A4") (pintype "bidirectional"))
      (node (ref "SLOT0") (pin "A6") (pinfunction "A6_A6") (pintype "bidirectional"))
      (node (ref "SLOT1") (pin "A4") (pinfunction "A4_A4") (pintype "bidirectional"))
      (node (ref "SLOT1") (pin "A6") (pinfunction "A6_A6") (pintype "bidirectional"))
      (node (ref "SLOT2") (pin "A4") (pinfunction "A4_A4") (pintype "bidirectional"))
      (node (ref "SLOT2") (pin "A6") (pinfunction "A6_A6") (pintype "bidirectional"))
      (node (ref "SLOT3") (pin "A4") (pinfunction "A4_A4") (pintype "bidirectional"))
      (node (ref "SLOT3") (pin "A6") (pinfunction "A6_A6") (pintype "bidirectional"))
      (node (ref "SLOT4") (pin "A4") (pinfunction "A4_A4") (pintype "bidirectional"))
      (node (ref "SLOT4") (pin "A6") (pinfunction "A6_A6") (pintype "bidirectional"))
      (node (ref "U$1") (pin "17") (pinfunction "+5V_17") (pintype "bidirectional"))
      (node (ref "U$1") (pin "41") (pinfunction "+5V_41") (pintype "bidirectional"))
    )
    (net (code "53") (name "A0") (class "Default")
      (node (ref "SLOT0") (pin "A1") (pinfunction "A1_A1") (pintype "bidirectional"))
      (node (ref "SLOT1") (pin "A1") (pinfunction "A1_A1") (pintype "bidirectional"))
      (node (ref "SLOT2") (pin "A1") (pinfunction "A1_A1") (pintype "bidirectional"))
      (node (ref "SLOT3") (pin "A1") (pinfunction "A1_A1") (pintype "bidirectional"))
      (node (ref "SLOT4") (pin "A1") (pinfunction "A1_A1") (pintype "bidirectional"))
      (node (ref "U$1") (pin "16") (pinfunction "A0_16") (pintype "bidirectional"))
      (node (ref "U$3") (pin "PA1") (pinfunction "A1_PA1") (pintype "bidirectional"))
    )
    (net (code "54") (name "A1") (class "Default")
      (node (ref "SLOT0") (pin "A3") (pinfunction "A3_A3") (pintype "bidirectional"))
      (node (ref "SLOT1") (pin "A3") (pinfunction "A3_A3") (pintype "bidirectional"))
      (node (ref "SLOT2") (pin "A3") (pinfunction "A3_A3") (pintype "bidirectional"))
      (node (ref "SLOT3") (pin "A3") (pinfunction "A3_A3") (pintype "bidirectional"))
      (node (ref "SLOT4") (pin "A3") (pinfunction "A3_A3") (pintype "bidirectional"))
      (node (ref "U$1") (pin "14") (pinfunction "A1_14") (pintype "bidirectional"))
      (node (ref "U$3") (pin "PB1") (pinfunction "B1_PB1") (pintype "bidirectional"))
    )
    (net (code "55") (name "A2") (class "Default")
      (node (ref "SLOT0") (pin "A5") (pinfunction "A5_A5") (pintype "bidirectional"))
      (node (ref "SLOT1") (pin "A5") (pinfunction "A5_A5") (pintype "bidirectional"))
      (node (ref "SLOT2") (pin "A5") (pinfunction "A5_A5") (pintype "bidirectional"))
      (node (ref "SLOT3") (pin "A5") (pinfunction "A5_A5") (pintype "bidirectional"))
      (node (ref "SLOT4") (pin "A5") (pinfunction "A5_A5") (pintype "bidirectional"))
      (node (ref "U$1") (pin "12") (pinfunction "A2_12") (pintype "bidirectional"))
      (node (ref "U$3") (pin "PA2") (pinfunction "A2_PA2") (pintype "bidirectional"))
    )
    (net (code "56") (name "A3") (class "Default")
      (node (ref "SLOT0") (pin "A7") (pinfunction "A7_A7") (pintype "bidirectional"))
      (node (ref "SLOT1") (pin "A7") (pinfunction "A7_A7") (pintype "bidirectional"))
      (node (ref "SLOT2") (pin "A7") (pinfunction "A7_A7") (pintype "bidirectional"))
      (node (ref "SLOT3") (pin "A7") (pinfunction "A7_A7") (pintype "bidirectional"))
      (node (ref "SLOT4") (pin "A7") (pinfunction "A7_A7") (pintype "bidirectional"))
      (node (ref "U$1") (pin "10") (pinfunction "A3_10") (pintype "bidirectional"))
      (node (ref "U$3") (pin "PB2") (pinfunction "B2_PB2") (pintype "bidirectional"))
    )
    (net (code "57") (name "A4") (class "Default")
      (node (ref "SLOT0") (pin "A9") (pinfunction "A9_A9") (pintype "bidirectional"))
      (node (ref "SLOT1") (pin "A9") (pinfunction "A9_A9") (pintype "bidirectional"))
      (node (ref "SLOT2") (pin "A9") (pinfunction "A9_A9") (pintype "bidirectional"))
      (node (ref "SLOT3") (pin "A9") (pinfunction "A9_A9") (pintype "bidirectional"))
      (node (ref "SLOT4") (pin "A9") (pinfunction "A9_A9") (pintype "bidirectional"))
      (node (ref "U$1") (pin "8") (pinfunction "A4_8") (pintype "bidirectional"))
      (node (ref "U$3") (pin "PA3") (pinfunction "A3_PA3") (pintype "bidirectional"))
    )
    (net (code "58") (name "A5") (class "Default")
      (node (ref "SLOT0") (pin "A11") (pinfunction "A11_A11") (pintype "bidirectional"))
      (node (ref "SLOT1") (pin "A11") (pinfunction "A11_A11") (pintype "bidirectional"))
      (node (ref "SLOT2") (pin "A11") (pinfunction "A11_A11") (pintype "bidirectional"))
      (node (ref "SLOT3") (pin "A11") (pinfunction "A11_A11") (pintype "bidirectional"))
      (node (ref "SLOT4") (pin "A11") (pinfunction "A11_A11") (pintype "bidirectional"))
      (node (ref "U$1") (pin "6") (pinfunction "A5_6") (pintype "bidirectional"))
      (node (ref "U$3") (pin "PB3") (pinfunction "B3_PB3") (pintype "bidirectional"))
    )
    (net (code "59") (name "A6") (class "Default")
      (node (ref "SLOT0") (pin "A13") (pinfunction "A13_A13") (pintype "bidirectional"))
      (node (ref "SLOT1") (pin "A13") (pinfunction "A13_A13") (pintype "bidirectional"))
      (node (ref "SLOT2") (pin "A13") (pinfunction "A13_A13") (pintype "bidirectional"))
      (node (ref "SLOT3") (pin "A13") (pinfunction "A13_A13") (pintype "bidirectional"))
      (node (ref "SLOT4") (pin "A13") (pinfunction "A13_A13") (pintype "bidirectional"))
      (node (ref "U$1") (pin "4") (pinfunction "A6_4") (pintype "bidirectional"))
      (node (ref "U$3") (pin "PA4") (pinfunction "A4_PA4") (pintype "bidirectional"))
    )
    (net (code "60") (name "A7") (class "Default")
      (node (ref "SLOT0") (pin "A15") (pinfunction "A15_A15") (pintype "bidirectional"))
      (node (ref "SLOT1") (pin "A15") (pinfunction "A15_A15") (pintype "bidirectional"))
      (node (ref "SLOT2") (pin "A15") (pinfunction "A15_A15") (pintype "bidirectional"))
      (node (ref "SLOT3") (pin "A15") (pinfunction "A15_A15") (pintype "bidirectional"))
      (node (ref "SLOT4") (pin "A15") (pinfunction "A15_A15") (pintype "bidirectional"))
      (node (ref "U$1") (pin "2") (pinfunction "A7_2") (pintype "bidirectional"))
      (node (ref "U$3") (pin "PB4") (pinfunction "B4_PB4") (pintype "bidirectional"))
    )
    (net (code "61") (name "A8") (class "Default")
      (node (ref "SLOT0") (pin "A17") (pinfunction "A17_A17") (pintype "bidirectional"))
      (node (ref "SLOT1") (pin "A17") (pinfunction "A17_A17") (pintype "bidirectional"))
      (node (ref "SLOT2") (pin "A17") (pinfunction "A17_A17") (pintype "bidirectional"))
      (node (ref "SLOT3") (pin "A17") (pinfunction "A17_A17") (pintype "bidirectional"))
      (node (ref "SLOT4") (pin "A17") (pinfunction "A17_A17") (pintype "bidirectional"))
      (node (ref "U$1") (pin "50") (pinfunction "A8_50") (pintype "bidirectional"))
      (node (ref "U$3") (pin "PA5") (pinfunction "A5_PA5") (pintype "bidirectional"))
    )
    (net (code "62") (name "A9") (class "Default")
      (node (ref "SLOT0") (pin "B1") (pinfunction "B1_B1") (pintype "bidirectional"))
      (node (ref "SLOT1") (pin "B1") (pinfunction "B1_B1") (pintype "bidirectional"))
      (node (ref "SLOT2") (pin "B1") (pinfunction "B1_B1") (pintype "bidirectional"))
      (node (ref "SLOT3") (pin "B1") (pinfunction "B1_B1") (pintype "bidirectional"))
      (node (ref "SLOT4") (pin "B1") (pinfunction "B1_B1") (pintype "bidirectional"))
      (node (ref "U$1") (pin "48") (pinfunction "A9_48") (pintype "bidirectional"))
      (node (ref "U$3") (pin "PB5") (pinfunction "B5_PB5") (pintype "bidirectional"))
    )
    (net (code "63") (name "A10") (class "Default")
      (node (ref "SLOT0") (pin "B3") (pinfunction "B3_B3") (pintype "bidirectional"))
      (node (ref "SLOT1") (pin "B3") (pinfunction "B3_B3") (pintype "bidirectional"))
      (node (ref "SLOT2") (pin "B3") (pinfunction "B3_B3") (pintype "bidirectional"))
      (node (ref "SLOT3") (pin "B3") (pinfunction "B3_B3") (pintype "bidirectional"))
      (node (ref "SLOT4") (pin "B3") (pinfunction "B3_B3") (pintype "bidirectional"))
      (node (ref "U$1") (pin "46") (pinfunction "A10_46") (pintype "bidirectional"))
      (node (ref "U$3") (pin "PA6") (pinfunction "A6_PA6") (pintype "bidirectional"))
    )
    (net (code "64") (name "A11") (class "Default")
      (node (ref "SLOT0") (pin "B5") (pinfunction "B5_B5") (pintype "bidirectional"))
      (node (ref "SLOT1") (pin "B5") (pinfunction "B5_B5") (pintype "bidirectional"))
      (node (ref "SLOT2") (pin "B5") (pinfunction "B5_B5") (pintype "bidirectional"))
      (node (ref "SLOT3") (pin "B5") (pinfunction "B5_B5") (pintype "bidirectional"))
      (node (ref "SLOT4") (pin "B5") (pinfunction "B5_B5") (pintype "bidirectional"))
      (node (ref "U$1") (pin "44") (pinfunction "A11_44") (pintype "bidirectional"))
      (node (ref "U$3") (pin "PB6") (pinfunction "B6_PB6") (pintype "bidirectional"))
    )
    (net (code "65") (name "A12") (class "Default")
      (node (ref "SLOT0") (pin "B7") (pinfunction "B7_B7") (pintype "bidirectional"))
      (node (ref "SLOT1") (pin "B7") (pinfunction "B7_B7") (pintype "bidirectional"))
      (node (ref "SLOT2") (pin "B7") (pinfunction "B7_B7") (pintype "bidirectional"))
      (node (ref "SLOT3") (pin "B7") (pinfunction "B7_B7") (pintype "bidirectional"))
      (node (ref "SLOT4") (pin "B7") (pinfunction "B7_B7") (pintype "bidirectional"))
      (node (ref "U$1") (pin "42") (pinfunction "A12_42") (pintype "bidirectional"))
      (node (ref "U$3") (pin "PA7") (pinfunction "A7_PA7") (pintype "bidirectional"))
    )
    (net (code "66") (name "A13") (class "Default")
      (node (ref "SLOT0") (pin "B9") (pinfunction "B9_B9") (pintype "bidirectional"))
      (node (ref "SLOT1") (pin "B9") (pinfunction "B9_B9") (pintype "bidirectional"))
      (node (ref "SLOT2") (pin "B9") (pinfunction "B9_B9") (pintype "bidirectional"))
      (node (ref "SLOT3") (pin "B9") (pinfunction "B9_B9") (pintype "bidirectional"))
      (node (ref "SLOT4") (pin "B9") (pinfunction "B9_B9") (pintype "bidirectional"))
      (node (ref "U$1") (pin "40") (pinfunction "A13_40") (pintype "bidirectional"))
      (node (ref "U$3") (pin "PB7") (pinfunction "B7_PB7") (pintype "bidirectional"))
    )
    (net (code "67") (name "A14") (class "Default")
      (node (ref "SLOT0") (pin "B11") (pinfunction "B11_B11") (pintype "bidirectional"))
      (node (ref "SLOT1") (pin "B11") (pinfunction "B11_B11") (pintype "bidirectional"))
      (node (ref "SLOT2") (pin "B11") (pinfunction "B11_B11") (pintype "bidirectional"))
      (node (ref "SLOT3") (pin "B11") (pinfunction "B11_B11") (pintype "bidirectional"))
      (node (ref "SLOT4") (pin "B11") (pinfunction "B11_B11") (pintype "bidirectional"))
      (node (ref "U$1") (pin "38") (pinfunction "A14_38") (pintype "bidirectional"))
      (node (ref "U$3") (pin "PA8") (pinfunction "A8_PA8") (pintype "bidirectional"))
    )
    (net (code "68") (name "A15") (class "Default")
      (node (ref "SLOT0") (pin "B13") (pinfunction "B13_B13") (pintype "bidirectional"))
      (node (ref "SLOT1") (pin "B13") (pinfunction "B13_B13") (pintype "bidirectional"))
      (node (ref "SLOT2") (pin "B13") (pinfunction "B13_B13") (pintype "bidirectional"))
      (node (ref "SLOT3") (pin "B13") (pinfunction "B13_B13") (pintype "bidirectional"))
      (node (ref "SLOT4") (pin "B13") (pinfunction "B13_B13") (pintype "bidirectional"))
      (node (ref "U$1") (pin "36") (pinfunction "A15_36") (pintype "bidirectional"))
      (node (ref "U$3") (pin "PB8") (pinfunction "B8_PB8") (pintype "bidirectional"))
    )
    (net (code "69") (name "AVALID") (class "Default")
      (node (ref "SLOT0") (pin "B15") (pinfunction "B15_B15") (pintype "bidirectional"))
      (node (ref "SLOT1") (pin "B15") (pinfunction "B15_B15") (pintype "bidirectional"))
      (node (ref "SLOT2") (pin "B15") (pinfunction "B15_B15") (pintype "bidirectional"))
      (node (ref "SLOT3") (pin "B15") (pinfunction "B15_B15") (pintype "bidirectional"))
      (node (ref "SLOT4") (pin "B15") (pinfunction "B15_B15") (pintype "bidirectional"))
    )
    (net (code "70") (name "CLK") (class "Default")
      (node (ref "U$1") (pin "29") (pinfunction "B02_29") (pintype "bidirectional"))
      (node (ref "U$3") (pin "PA9") (pinfunction "A9_PA9") (pintype "bidirectional"))
    )
    (net (code "71") (name "D0") (class "Default")
      (node (ref "SLOT0") (pin "A10") (pinfunction "A10_A10") (pintype "bidirectional"))
      (node (ref "SLOT1") (pin "A10") (pinfunction "A10_A10") (pintype "bidirectional"))
      (node (ref "SLOT2") (pin "A10") (pinfunction "A10_A10") (pintype "bidirectional"))
      (node (ref "SLOT3") (pin "A10") (pinfunction "A10_A10") (pintype "bidirectional"))
      (node (ref "SLOT4") (pin "A10") (pinfunction "A10_A10") (pintype "bidirectional"))
      (node (ref "U$1") (pin "15") (pinfunction "D0_15") (pintype "bidirectional"))
      (node (ref "U$3") (pin "PB9") (pinfunction "B9_PB9") (pintype "bidirectional"))
    )
    (net (code "72") (name "D1") (class "Default")
      (node (ref "SLOT0") (pin "A12") (pinfunction "A12_A12") (pintype "bidirectional"))
      (node (ref "SLOT1") (pin "A12") (pinfunction "A12_A12") (pintype "bidirectional"))
      (node (ref "SLOT2") (pin "A12") (pinfunction "A12_A12") (pintype "bidirectional"))
      (node (ref "SLOT3") (pin "A12") (pinfunction "A12_A12") (pintype "bidirectional"))
      (node (ref "SLOT4") (pin "A12") (pinfunction "A12_A12") (pintype "bidirectional"))
      (node (ref "U$1") (pin "13") (pinfunction "D1_13") (pintype "bidirectional"))
      (node (ref "U$3") (pin "PA10") (pinfunction "A10_PA10") (pintype "bidirectional"))
    )
    (net (code "73") (name "D2") (class "Default")
      (node (ref "SLOT0") (pin "A14") (pinfunction "A14_A14") (pintype "bidirectional"))
      (node (ref "SLOT1") (pin "A14") (pinfunction "A14_A14") (pintype "bidirectional"))
      (node (ref "SLOT2") (pin "A14") (pinfunction "A14_A14") (pintype "bidirectional"))
      (node (ref "SLOT3") (pin "A14") (pinfunction "A14_A14") (pintype "bidirectional"))
      (node (ref "SLOT4") (pin "A14") (pinfunction "A14_A14") (pintype "bidirectional"))
      (node (ref "U$1") (pin "11") (pinfunction "D2_11") (pintype "bidirectional"))
      (node (ref "U$3") (pin "PB10") (pinfunction "B10_PB10") (pintype "bidirectional"))
    )
    (net (code "74") (name "D3") (class "Default")
      (node (ref "SLOT0") (pin "A16") (pinfunction "A16_A16") (pintype "bidirectional"))
      (node (ref "SLOT1") (pin "A16") (pinfunction "A16_A16") (pintype "bidirectional"))
      (node (ref "SLOT2") (pin "A16") (pinfunction "A16_A16") (pintype "bidirectional"))
      (node (ref "SLOT3") (pin "A16") (pinfunction "A16_A16") (pintype "bidirectional"))
      (node (ref "SLOT4") (pin "A16") (pinfunction "A16_A16") (pintype "bidirectional"))
      (node (ref "U$1") (pin "9") (pinfunction "D3_9") (pintype "bidirectional"))
      (node (ref "U$3") (pin "PA11") (pinfunction "A11_PA11") (pintype "bidirectional"))
    )
    (net (code "75") (name "D4") (class "Default")
      (node (ref "SLOT0") (pin "A18") (pinfunction "A18_A18") (pintype "bidirectional"))
      (node (ref "SLOT1") (pin "A18") (pinfunction "A18_A18") (pintype "bidirectional"))
      (node (ref "SLOT2") (pin "A18") (pinfunction "A18_A18") (pintype "bidirectional"))
      (node (ref "SLOT3") (pin "A18") (pinfunction "A18_A18") (pintype "bidirectional"))
      (node (ref "SLOT4") (pin "A18") (pinfunction "A18_A18") (pintype "bidirectional"))
      (node (ref "U$1") (pin "7") (pinfunction "D4_7") (pintype "bidirectional"))
      (node (ref "U$3") (pin "PB11") (pinfunction "B11_PB11") (pintype "bidirectional"))
    )
    (net (code "76") (name "D5") (class "Default")
      (node (ref "SLOT0") (pin "B2") (pinfunction "B2_B2") (pintype "bidirectional"))
      (node (ref "SLOT1") (pin "B2") (pinfunction "B2_B2") (pintype "bidirectional"))
      (node (ref "SLOT2") (pin "B2") (pinfunction "B2_B2") (pintype "bidirectional"))
      (node (ref "SLOT3") (pin "B2") (pinfunction "B2_B2") (pintype "bidirectional"))
      (node (ref "SLOT4") (pin "B2") (pinfunction "B2_B2") (pintype "bidirectional"))
      (node (ref "U$1") (pin "5") (pinfunction "D5_5") (pintype "bidirectional"))
      (node (ref "U$3") (pin "PA12") (pinfunction "A12_PA12") (pintype "bidirectional"))
    )
    (net (code "77") (name "D6") (class "Default")
      (node (ref "SLOT0") (pin "B4") (pinfunction "B4_B4") (pintype "bidirectional"))
      (node (ref "SLOT1") (pin "B4") (pinfunction "B4_B4") (pintype "bidirectional"))
      (node (ref "SLOT2") (pin "B4") (pinfunction "B4_B4") (pintype "bidirectional"))
      (node (ref "SLOT3") (pin "B4") (pinfunction "B4_B4") (pintype "bidirectional"))
      (node (ref "SLOT4") (pin "B4") (pinfunction "B4_B4") (pintype "bidirectional"))
      (node (ref "U$1") (pin "3") (pinfunction "D6_3") (pintype "bidirectional"))
      (node (ref "U$3") (pin "PB12") (pinfunction "B12_PB12") (pintype "bidirectional"))
    )
    (net (code "78") (name "D7") (class "Default")
      (node (ref "SLOT0") (pin "B6") (pinfunction "B6_B6") (pintype "bidirectional"))
      (node (ref "SLOT1") (pin "B6") (pinfunction "B6_B6") (pintype "bidirectional"))
      (node (ref "SLOT2") (pin "B6") (pinfunction "B6_B6") (pintype "bidirectional"))
      (node (ref "SLOT3") (pin "B6") (pinfunction "B6_B6") (pintype "bidirectional"))
      (node (ref "SLOT4") (pin "B6") (pinfunction "B6_B6") (pintype "bidirectional"))
      (node (ref "U$1") (pin "1") (pinfunction "D7_1") (pintype "bidirectional"))
      (node (ref "U$3") (pin "PA13") (pinfunction "A13_PA13") (pintype "bidirectional"))
    )
    (net (code "79") (name "GND") (class "Default")
      (node (ref "C1") (pin "2") (pinfunction "2_2") (pintype "passive"))
      (node (ref "C53") (pin "2") (pinfunction "2_2") (pintype "passive"))
      (node (ref "C55") (pin "2") (pinfunction "2_2") (pintype "passive"))
      (node (ref "C56") (pin "1") (pinfunction "1_1") (pintype "passive"))
      (node (ref "C81") (pin "2") (pinfunction "2_2") (pintype "passive"))
      (node (ref "LD0") (pin "C") (pinfunction "C_C") (pintype "passive"))
      (node (ref "LD1") (pin "C") (pinfunction "C_C") (pintype "passive"))
      (node (ref "LD2") (pin "C") (pinfunction "C_C") (pintype "passive"))
      (node (ref "LD3") (pin "C") (pinfunction "C_C") (pintype "passive"))
      (node (ref "LD4") (pin "C") (pinfunction "C_C") (pintype "passive"))
      (node (ref "R61") (pin "2") (pinfunction "2_2") (pintype "passive"))
      (node (ref "R62") (pin "2") (pinfunction "2_2") (pintype "passive"))
      (node (ref "R63") (pin "2") (pinfunction "2_2") (pintype "passive"))
      (node (ref "R64") (pin "2") (pinfunction "2_2") (pintype "passive"))
      (node (ref "R65") (pin "2") (pinfunction "2_2") (pintype "passive"))
      (node (ref "SLOT0") (pin "B17") (pinfunction "B17_B17") (pintype "bidirectional"))
      (node (ref "SLOT0") (pin "B18") (pinfunction "B18_B18") (pintype "bidirectional"))
      (node (ref "SLOT0") (pin "B8") (pinfunction "B8_B8") (pintype "bidirectional"))
      (node (ref "SLOT1") (pin "B17") (pinfunction "B17_B17") (pintype "bidirectional"))
      (node (ref "SLOT1") (pin "B18") (pinfunction "B18_B18") (pintype "bidirectional"))
      (node (ref "SLOT1") (pin "B8") (pinfunction "B8_B8") (pintype "bidirectional"))
      (node (ref "SLOT2") (pin "B17") (pinfunction "B17_B17") (pintype "bidirectional"))
      (node (ref "SLOT2") (pin "B18") (pinfunction "B18_B18") (pintype "bidirectional"))
      (node (ref "SLOT2") (pin "B8") (pinfunction "B8_B8") (pintype "bidirectional"))
      (node (ref "SLOT3") (pin "B17") (pinfunction "B17_B17") (pintype "bidirectional"))
      (node (ref "SLOT3") (pin "B18") (pinfunction "B18_B18") (pintype "bidirectional"))
      (node (ref "SLOT3") (pin "B8") (pinfunction "B8_B8") (pintype "bidirectional"))
      (node (ref "SLOT4") (pin "B17") (pinfunction "B17_B17") (pintype "bidirectional"))
      (node (ref "SLOT4") (pin "B18") (pinfunction "B18_B18") (pintype "bidirectional"))
      (node (ref "SLOT4") (pin "B8") (pinfunction "B8_B8") (pintype "bidirectional"))
      (node (ref "U$1") (pin "18") (pinfunction "GND_18") (pintype "bidirectional"))
      (node (ref "U$1") (pin "35") (pinfunction "GND_35") (pintype "bidirectional"))
      (node (ref "U$3") (pin "SHIELD1") (pinfunction "SHIELD_SHIELD1") (pintype "bidirectional"))
      (node (ref "U$3") (pin "SHIELD2") (pinfunction "SHIELD_SHIELD2") (pintype "bidirectional"))
      (node (ref "U$3") (pin "SHIELD3") (pinfunction "SHIELD_SHIELD3") (pintype "bidirectional"))
      (node (ref "U$3") (pin "SHIELD4") (pinfunction "SHIELD_SHIELD4") (pintype "bidirectional"))
      (node (ref "U$3") (pin "SHIELD5") (pinfunction "SHIELD_SHIELD5") (pintype "bidirectional"))
      (node (ref "U$3") (pin "SHIELD6") (pinfunction "SHIELD_SHIELD6") (pintype "bidirectional"))
    )
    (net (code "80") (name "Net-(LD0-PadA)") (class "Default")
      (node (ref "LD0") (pin "A") (pinfunction "A_A") (pintype "passive"))
      (node (ref "R27") (pin "2") (pinfunction "2_2") (pintype "passive"))
    )
    (net (code "81") (name "Net-(LD1-PadA)") (class "Default")
      (node (ref "LD1") (pin "A") (pinfunction "A_A") (pintype "passive"))
      (node (ref "R98") (pin "2") (pinfunction "2_2") (pintype "passive"))
    )
    (net (code "82") (name "Net-(LD2-PadA)") (class "Default")
      (node (ref "LD2") (pin "A") (pinfunction "A_A") (pintype "passive"))
      (node (ref "R101") (pin "2") (pinfunction "2_2") (pintype "passive"))
    )
    (net (code "83") (name "Net-(LD3-PadA)") (class "Default")
      (node (ref "LD3") (pin "A") (pinfunction "A_A") (pintype "passive"))
      (node (ref "R104") (pin "2") (pinfunction "2_2") (pintype "passive"))
    )
    (net (code "84") (name "Net-(LD4-PadA)") (class "Default")
      (node (ref "LD4") (pin "A") (pinfunction "A_A") (pintype "passive"))
      (node (ref "R107") (pin "2") (pinfunction "2_2") (pintype "passive"))
    )
    (net (code "85") (name "Net-(R101-Pad1)") (class "Default")
      (node (ref "R101") (pin "1") (pinfunction "1_1") (pintype "passive"))
      (node (ref "R63") (pin "1") (pinfunction "1_1") (pintype "passive"))
      (node (ref "SLOT2") (pin "A8") (pinfunction "A8_A8") (pintype "bidirectional"))
    )
    (net (code "86") (name "Net-(R104-Pad1)") (class "Default")
      (node (ref "R104") (pin "1") (pinfunction "1_1") (pintype "passive"))
      (node (ref "R64") (pin "1") (pinfunction "1_1") (pintype "passive"))
      (node (ref "SLOT3") (pin "A8") (pinfunction "A8_A8") (pintype "bidirectional"))
    )
    (net (code "87") (name "Net-(R107-Pad1)") (class "Default")
      (node (ref "R107") (pin "1") (pinfunction "1_1") (pintype "passive"))
      (node (ref "R65") (pin "1") (pinfunction "1_1") (pintype "passive"))
      (node (ref "SLOT4") (pin "A8") (pinfunction "A8_A8") (pintype "bidirectional"))
    )
    (net (code "88") (name "PRESENT0") (class "Default")
      (node (ref "R62") (pin "1") (pinfunction "1_1") (pintype "passive"))
      (node (ref "R98") (pin "1") (pinfunction "1_1") (pintype "passive"))
      (node (ref "SLOT0") (pin "A8") (pinfunction "A8_A8") (pintype "bidirectional"))
    )
    (net (code "89") (name "PRESENT1") (class "Default")
      (node (ref "R27") (pin "1") (pinfunction "1_1") (pintype "passive"))
      (node (ref "R61") (pin "1") (pinfunction "1_1") (pintype "passive"))
      (node (ref "SLOT1") (pin "A8") (pinfunction "A8_A8") (pintype "bidirectional"))
    )
    (net (code "90") (name "RD4") (class "Default")
      (node (ref "U$1") (pin "43") (pinfunction "RD4_43") (pintype "bidirectional"))
      (node (ref "U$3") (pin "PB15") (pinfunction "B15_PB15") (pintype "bidirectional"))
    )
    (net (code "91") (name "RD5") (class "Default")
      (node (ref "U$1") (pin "45") (pinfunction "RD5_45") (pintype "bidirectional"))
      (node (ref "U$3") (pin "PA16") (pinfunction "A16_PA16") (pintype "bidirectional"))
    )
    (net (code "92") (name "R{slash}~{W}") (class "Default")
      (node (ref "U$1") (pin "27") (pinfunction "R/~{W}_27") (pintype "bidirectional"))
      (node (ref "U$3") (pin "PB17") (pinfunction "B17_PB17") (pintype "bidirectional"))
    )
    (net (code "93") (name "SPI0_CLK") (class "Default")
      (node (ref "SLOT0") (pin "B12") (pinfunction "B12_B12") (pintype "bidirectional"))
    )
    (net (code "94") (name "SPI0_MISO") (class "Default")
      (node (ref "SLOT0") (pin "B14") (pinfunction "B14_B14") (pintype "bidirectional"))
    )
    (net (code "95") (name "SPI0_MOSI") (class "Default")
      (node (ref "SLOT0") (pin "B16") (pinfunction "B16_B16") (pintype "bidirectional"))
    )
    (net (code "96") (name "SPI1_CLK") (class "Default")
      (node (ref "SLOT1") (pin "B12") (pinfunction "B12_B12") (pintype "bidirectional"))
    )
    (net (code "97") (name "SPI1_MISO") (class "Default")
      (node (ref "SLOT1") (pin "B14") (pinfunction "B14_B14") (pintype "bidirectional"))
    )
    (net (code "98") (name "SPI1_MOSI") (class "Default")
      (node (ref "SLOT1") (pin "B16") (pinfunction "B16_B16") (pintype "bidirectional"))
    )
    (net (code "99") (name "SPI2_CLK") (class "Default")
      (node (ref "SLOT2") (pin "B12") (pinfunction "B12_B12") (pintype "bidirectional"))
    )
    (net (code "100") (name "SPI2_MISO") (class "Default")
      (node (ref "SLOT2") (pin "B14") (pinfunction "B14_B14") (pintype "bidirectional"))
    )
    (net (code "101") (name "SPI2_MOSI") (class "Default")
      (node (ref "SLOT2") (pin "B16") (pinfunction "B16_B16") (pintype "bidirectional"))
    )
    (net (code "102") (name "SPI3_CLK") (class "Default")
      (node (ref "SLOT3") (pin "B12") (pinfunction "B12_B12") (pintype "bidirectional"))
    )
    (net (code "103") (name "SPI3_MISO") (class "Default")
      (node (ref "SLOT3") (pin "B14") (pinfunction "B14_B14") (pintype "bidirectional"))
    )
    (net (code "104") (name "SPI3_MOSI") (class "Default")
      (node (ref "SLOT3") (pin "B16") (pinfunction "B16_B16") (pintype "bidirectional"))
    )
    (net (code "105") (name "SPI4_CLK") (class "Default")
      (node (ref "SLOT4") (pin "B12") (pinfunction "B12_B12") (pintype "bidirectional"))
    )
    (net (code "106") (name "SPI4_MISO") (class "Default")
      (node (ref "SLOT4") (pin "B14") (pinfunction "B14_B14") (pintype "bidirectional"))
    )
    (net (code "107") (name "SPI4_MOSI") (class "Default")
      (node (ref "SLOT4") (pin "B16") (pinfunction "B16_B16") (pintype "bidirectional"))
    )
    (net (code "108") (name "unconnected-(IC4-AGND-Pad41)") (class "Default")
      (node (ref "IC4") (pin "41") (pinfunction "AGND_41") (pintype "bidirectional"))
    )
    (net (code "109") (name "unconnected-(IC4-BOUT-Pad34)") (class "Default")
      (node (ref "IC4") (pin "34") (pinfunction "BOUT_34") (pintype "bidirectional"))
    )
    (net (code "110") (name "unconnected-(IC4-BUCK1IN-Pad8)") (class "Default")
      (node (ref "IC4") (pin "8") (pinfunction "BUCK1IN_8") (pintype "bidirectional"))
    )
    (net (code "111") (name "unconnected-(IC4-BUCK2IN-Pad12)") (class "Default")
      (node (ref "IC4") (pin "12") (pinfunction "BUCK2IN_12") (pintype "bidirectional"))
    )
    (net (code "112") (name "unconnected-(IC4-BUCK3IN-Pad28)") (class "Default")
      (node (ref "IC4") (pin "28") (pinfunction "BUCK3IN_28") (pintype "bidirectional"))
    )
    (net (code "113") (name "unconnected-(IC4-BUCK4IN-Pad24)") (class "Default")
      (node (ref "IC4") (pin "24") (pinfunction "BUCK4IN_24") (pintype "bidirectional"))
    )
    (net (code "114") (name "unconnected-(IC4-EP-Pad45)") (class "Default")
      (node (ref "IC4") (pin "45") (pinfunction "EP_45") (pintype "bidirectional"))
    )
    (net (code "115") (name "unconnected-(IC4-GNDLDO-Pad15)") (class "Default")
      (node (ref "IC4") (pin "15") (pinfunction "GNDLDO_15") (pintype "bidirectional"))
    )
    (net (code "116") (name "unconnected-(IC4-INTLDO-Pad40)") (class "Default")
      (node (ref "IC4") (pin "40") (pinfunction "INTLDO_40") (pintype "bidirectional"))
    )
    (net (code "117") (name "unconnected-(IC4-INTN-Pad43)") (class "Default")
      (node (ref "IC4") (pin "43") (pinfunction "INTN_43") (pintype "bidirectional"))
    )
    (net (code "118") (name "unconnected-(IC4-LDO1OUT-Pad23)") (class "Default")
      (node (ref "IC4") (pin "23") (pinfunction "LDO1OUT_23") (pintype "bidirectional"))
    )
    (net (code "119") (name "unconnected-(IC4-LDO2OUT-Pad18)") (class "Default")
      (node (ref "IC4") (pin "18") (pinfunction "LDO2OUT_18") (pintype "bidirectional"))
    )
    (net (code "120") (name "unconnected-(IC4-LDO3IN-Pad13)") (class "Default")
      (node (ref "IC4") (pin "13") (pinfunction "LDO3IN_13") (pintype "bidirectional"))
    )
    (net (code "121") (name "unconnected-(IC4-LDO3OUT-Pad14)") (class "Default")
      (node (ref "IC4") (pin "14") (pinfunction "LDO3OUT_14") (pintype "bidirectional"))
    )
    (net (code "122") (name "unconnected-(IC4-LDO4OUT-Pad39)") (class "Default")
      (node (ref "IC4") (pin "39") (pinfunction "LDO4OUT_39") (pintype "bidirectional"))
    )
    (net (code "123") (name "unconnected-(IC4-LDO5OUT-Pad20)") (class "Default")
      (node (ref "IC4") (pin "20") (pinfunction "LDO5OUT_20") (pintype "bidirectional"))
    )
    (net (code "124") (name "unconnected-(IC4-LDO6OUT-Pad21)") (class "Default")
      (node (ref "IC4") (pin "21") (pinfunction "LDO6OUT_21") (pintype "bidirectional"))
    )
    (net (code "125") (name "unconnected-(IC4-LDO16IN-Pad22)") (class "Default")
      (node (ref "IC4") (pin "22") (pinfunction "LDO16IN_22") (pintype "bidirectional"))
    )
    (net (code "126") (name "unconnected-(IC4-LDO25IN-Pad19)") (class "Default")
      (node (ref "IC4") (pin "19") (pinfunction "LDO25IN_19") (pintype "bidirectional"))
    )
    (net (code "127") (name "unconnected-(IC4-PGBOOST-Pad32)") (class "Default")
      (node (ref "IC4") (pin "32") (pinfunction "PGBOOST_32") (pintype "bidirectional"))
    )
    (net (code "128") (name "unconnected-(IC4-PGND1-Pad6)") (class "Default")
      (node (ref "IC4") (pin "6") (pinfunction "PGND1_6") (pintype "bidirectional"))
    )
    (net (code "129") (name "unconnected-(IC4-PGND2-Pad10)") (class "Default")
      (node (ref "IC4") (pin "10") (pinfunction "PGND2_10") (pintype "bidirectional"))
    )
    (net (code "130") (name "unconnected-(IC4-PGND3-Pad30)") (class "Default")
      (node (ref "IC4") (pin "30") (pinfunction "PGND3_30") (pintype "bidirectional"))
    )
    (net (code "131") (name "unconnected-(IC4-PGND4-Pad26)") (class "Default")
      (node (ref "IC4") (pin "26") (pinfunction "PGND4_26") (pintype "bidirectional"))
    )
    (net (code "132") (name "unconnected-(IC4-PONKEYN-Pad17)") (class "Default")
      (node (ref "IC4") (pin "17") (pinfunction "PONKEYN_17") (pintype "bidirectional"))
    )
    (net (code "133") (name "unconnected-(IC4-PWRCTRL-Pad44)") (class "Default")
      (node (ref "IC4") (pin "44") (pinfunction "PWRCTRL_44") (pintype "bidirectional"))
    )
    (net (code "134") (name "unconnected-(IC4-RSTN-Pad1)") (class "Default")
      (node (ref "IC4") (pin "1") (pinfunction "RSTN_1") (pintype "bidirectional"))
    )
    (net (code "135") (name "unconnected-(IC4-SCL-Pad4)") (class "Default")
      (node (ref "IC4") (pin "4") (pinfunction "SCL_4") (pintype "bidirectional"))
    )
    (net (code "136") (name "unconnected-(IC4-SDA-Pad3)") (class "Default")
      (node (ref "IC4") (pin "3") (pinfunction "SDA_3") (pintype "bidirectional"))
    )
    (net (code "137") (name "unconnected-(IC4-SWIN-Pad37)") (class "Default")
      (node (ref "IC4") (pin "37") (pinfunction "SWIN_37") (pintype "bidirectional"))
    )
    (net (code "138") (name "unconnected-(IC4-SWOUT-Pad38)") (class "Default")
      (node (ref "IC4") (pin "38") (pinfunction "SWOUT_38") (pintype "bidirectional"))
    )
    (net (code "139") (name "unconnected-(IC4-VBUSOTG-Pad35)") (class "Default")
      (node (ref "IC4") (pin "35") (pinfunction "VBUSOTG_35") (pintype "bidirectional"))
    )
    (net (code "140") (name "unconnected-(IC4-VIN-Pad36)") (class "Default")
      (node (ref "IC4") (pin "36") (pinfunction "VIN_36") (pintype "bidirectional"))
    )
    (net (code "141") (name "unconnected-(IC4-VIO-Pad42)") (class "Default")
      (node (ref "IC4") (pin "42") (pinfunction "VIO_42") (pintype "bidirectional"))
    )
    (net (code "142") (name "unconnected-(IC4-VLX1-Pad7)") (class "Default")
      (node (ref "IC4") (pin "7") (pinfunction "VLX1_7") (pintype "bidirectional"))
    )
    (net (code "143") (name "unconnected-(IC4-VLX2-Pad11)") (class "Default")
      (node (ref "IC4") (pin "11") (pinfunction "VLX2_11") (pintype "bidirectional"))
    )
    (net (code "144") (name "unconnected-(IC4-VLX3-Pad29)") (class "Default")
      (node (ref "IC4") (pin "29") (pinfunction "VLX3_29") (pintype "bidirectional"))
    )
    (net (code "145") (name "unconnected-(IC4-VLX4-Pad25)") (class "Default")
      (node (ref "IC4") (pin "25") (pinfunction "VLX4_25") (pintype "bidirectional"))
    )
    (net (code "146") (name "unconnected-(IC4-VLXBST-Pad33)") (class "Default")
      (node (ref "IC4") (pin "33") (pinfunction "VLXBST_33") (pintype "bidirectional"))
    )
    (net (code "147") (name "unconnected-(IC4-VOUT1-Pad5)") (class "Default")
      (node (ref "IC4") (pin "5") (pinfunction "VOUT1_5") (pintype "bidirectional"))
    )
    (net (code "148") (name "unconnected-(IC4-VOUT2-Pad9)") (class "Default")
      (node (ref "IC4") (pin "9") (pinfunction "VOUT2_9") (pintype "bidirectional"))
    )
    (net (code "149") (name "unconnected-(IC4-VOUT3-Pad31)") (class "Default")
      (node (ref "IC4") (pin "31") (pinfunction "VOUT3_31") (pintype "bidirectional"))
    )
    (net (code "150") (name "unconnected-(IC4-VOUT4-Pad27)") (class "Default")
      (node (ref "IC4") (pin "27") (pinfunction "VOUT4_27") (pintype "bidirectional"))
    )
    (net (code "151") (name "unconnected-(IC4-VREFDDR-Pad16)") (class "Default")
      (node (ref "IC4") (pin "16") (pinfunction "VREFDDR_16") (pintype "bidirectional"))
    )
    (net (code "152") (name "unconnected-(IC4-WAKEUP-Pad2)") (class "Default")
      (node (ref "IC4") (pin "2") (pinfunction "WAKEUP_2") (pintype "bidirectional"))
    )
    (net (code "153") (name "unconnected-(J1---Pad-1)") (class "Default")
      (node (ref "J1") (pin "-1") (pinfunction "-_-1") (pintype "bidirectional"))
    )
    (net (code "154") (name "unconnected-(J1-CDN-Pad-2)") (class "Default")
      (node (ref "J1") (pin "-2") (pinfunction "CDN_-2") (pintype "bidirectional"))
    )
    (net (code "155") (name "unconnected-(J1-Pad+)") (class "Default")
      (node (ref "J1") (pin "+") (pinfunction "+_+") (pintype "bidirectional"))
    )
    (net (code "156") (name "unconnected-(U$1-+12V-Pad49)") (class "Default")
      (node (ref "U$1") (pin "49") (pinfunction "+12V_49") (pintype "bidirectional"))
    )
    (net (code "157") (name "unconnected-(U$1-L-IN-Pad34)") (class "Default")
      (node (ref "U$1") (pin "34") (pinfunction "L-IN_34") (pintype "bidirectional"))
    )
    (net (code "158") (name "unconnected-(U$1-M1-Pad19)") (class "Default")
      (node (ref "U$1") (pin "19") (pinfunction "M1_19") (pintype "bidirectional"))
    )
    (net (code "159") (name "unconnected-(U$1-R-IN-Pad32)") (class "Default")
      (node (ref "U$1") (pin "32") (pinfunction "R-IN_32") (pintype "bidirectional"))
    )
    (net (code "160") (name "unconnected-(U$1-VB-Pad21)") (class "Default")
      (node (ref "U$1") (pin "21") (pinfunction "VB_21") (pintype "bidirectional"))
    )
    (net (code "161") (name "unconnected-(U$1-~{CI}-Pad28)") (class "Default")
      (node (ref "U$1") (pin "28") (pinfunction "~{CI}_28") (pintype "bidirectional"))
    )
    (net (code "162") (name "unconnected-(U$1-~{D1XX}-Pad24)") (class "Default")
      (node (ref "U$1") (pin "24") (pinfunction "~{D1XX}_24") (pintype "bidirectional"))
    )
    (net (code "163") (name "unconnected-(U$1-~{D6XX}-Pad22)") (class "Default")
      (node (ref "U$1") (pin "22") (pinfunction "~{D6XX}_22") (pintype "bidirectional"))
    )
    (net (code "164") (name "unconnected-(U$1-~{D7XX}-Pad20)") (class "Default")
      (node (ref "U$1") (pin "20") (pinfunction "~{D7XX}_20") (pintype "bidirectional"))
    )
    (net (code "165") (name "unconnected-(U$1-~{REF}-Pad47)") (class "Default")
      (node (ref "U$1") (pin "47") (pinfunction "~{REF}_47") (pintype "bidirectional"))
    )
    (net (code "166") (name "unconnected-(U$2A-PB0-Pad61)") (class "Default")
      (node (ref "U$2") (pin "61") (pinfunction "PB0_61") (pintype "bidirectional"))
    )
    (net (code "167") (name "unconnected-(U$2A-PB1-Pad62)") (class "Default")
      (node (ref "U$2") (pin "62") (pinfunction "PB1_62") (pintype "bidirectional"))
    )
    (net (code "168") (name "unconnected-(U$2A-PF10-Pad31)") (class "Default")
      (node (ref "U$2") (pin "31") (pinfunction "PF10_31") (pintype "bidirectional"))
    )
    (net (code "169") (name "unconnected-(U$2B-PG3-Pad130)") (class "Default")
      (node (ref "U$2") (pin "130") (pinfunction "PG3_130") (pintype "bidirectional"))
    )
    (net (code "170") (name "unconnected-(U$2B-PG6-Pad133)") (class "Default")
      (node (ref "U$2") (pin "133") (pinfunction "PG6_133") (pintype "bidirectional"))
    )
    (net (code "171") (name "unconnected-(U$2B-PG7-Pad134)") (class "Default")
      (node (ref "U$2") (pin "134") (pinfunction "PG7_134") (pintype "bidirectional"))
    )
    (net (code "172") (name "unconnected-(U$2B-PG9-Pad178)") (class "Default")
      (node (ref "U$2") (pin "178") (pinfunction "PG9_178") (pintype "bidirectional"))
    )
    (net (code "173") (name "unconnected-(U$2B-PG10-Pad179)") (class "Default")
      (node (ref "U$2") (pin "179") (pinfunction "PG10_179") (pintype "bidirectional"))
    )
    (net (code "174") (name "unconnected-(U$2B-PG11-Pad180)") (class "Default")
      (node (ref "U$2") (pin "180") (pinfunction "PG11_180") (pintype "bidirectional"))
    )
    (net (code "175") (name "unconnected-(U$2B-PG12-Pad181)") (class "Default")
      (node (ref "U$2") (pin "181") (pinfunction "PG12_181") (pintype "bidirectional"))
    )
    (net (code "176") (name "unconnected-(U$2B-PG13-Pad182)") (class "Default")
      (node (ref "U$2") (pin "182") (pinfunction "PG13_182") (pintype "bidirectional"))
    )
    (net (code "177") (name "unconnected-(U$2B-PG14-Pad183)") (class "Default")
      (node (ref "U$2") (pin "183") (pinfunction "PG14_183") (pintype "bidirectional"))
    )
    (net (code "178") (name "unconnected-(U$2C-PB9-Pad199)") (class "Default")
      (node (ref "U$2") (pin "199") (pinfunction "PB9_199") (pintype "bidirectional"))
    )
    (net (code "179") (name "unconnected-(U$2C-PB10-Pad90)") (class "Default")
      (node (ref "U$2") (pin "90") (pinfunction "PB10_90") (pintype "bidirectional"))
    )
    (net (code "180") (name "unconnected-(U$2C-PB15-Pad107)") (class "Default")
      (node (ref "U$2") (pin "107") (pinfunction "PB15_107") (pintype "bidirectional"))
    )
    (net (code "181") (name "unconnected-(U$2D-PD11-Pad111)") (class "Default")
      (node (ref "U$2") (pin "111") (pinfunction "PD11_111") (pintype "bidirectional"))
    )
    (net (code "182") (name "unconnected-(U$2D-PD12-Pad112)") (class "Default")
      (node (ref "U$2") (pin "112") (pinfunction "PD12_112") (pintype "bidirectional"))
    )
    (net (code "183") (name "unconnected-(U$2D-PD13-Pad113)") (class "Default")
      (node (ref "U$2") (pin "113") (pinfunction "PD13_113") (pintype "bidirectional"))
    )
    (net (code "184") (name "unconnected-(U$2E-PH2-Pad46)") (class "Default")
      (node (ref "U$2") (pin "46") (pinfunction "PH2_46") (pintype "bidirectional"))
    )
    (net (code "185") (name "unconnected-(U$2E-PH3-Pad47)") (class "Default")
      (node (ref "U$2") (pin "47") (pinfunction "PH3_47") (pintype "bidirectional"))
    )
    (net (code "186") (name "unconnected-(U$2E-PH4-Pad48)") (class "Default")
      (node (ref "U$2") (pin "48") (pinfunction "PH4_48") (pintype "bidirectional"))
    )
    (net (code "187") (name "unconnected-(U$2F-PA1-Pad44)") (class "Default")
      (node (ref "U$2") (pin "44") (pinfunction "PA1_44") (pintype "bidirectional"))
    )
    (net (code "188") (name "unconnected-(U$2F-PA2-Pad45)") (class "Default")
      (node (ref "U$2") (pin "45") (pinfunction "PA2_45") (pintype "bidirectional"))
    )
    (net (code "189") (name "unconnected-(U$2F-PA7-Pad56)") (class "Default")
      (node (ref "U$2") (pin "56") (pinfunction "PA7_56") (pintype "bidirectional"))
    )
    (net (code "190") (name "unconnected-(U$2F-PB11-Pad91)") (class "Default")
      (node (ref "U$2") (pin "91") (pinfunction "PB11_91") (pintype "bidirectional"))
    )
    (net (code "191") (name "unconnected-(U$2F-PB12-Pad104)") (class "Default")
      (node (ref "U$2") (pin "104") (pinfunction "PB12_104") (pintype "bidirectional"))
    )
    (net (code "192") (name "unconnected-(U$2F-PB13-Pad105)") (class "Default")
      (node (ref "U$2") (pin "105") (pinfunction "PB13_105") (pintype "bidirectional"))
    )
    (net (code "193") (name "unconnected-(U$2F-PC1-Pad36)") (class "Default")
      (node (ref "U$2") (pin "36") (pinfunction "PC1_36") (pintype "bidirectional"))
    )
    (net (code "194") (name "unconnected-(U$2F-PC4-Pad57)") (class "Default")
      (node (ref "U$2") (pin "57") (pinfunction "PC4_57") (pintype "bidirectional"))
    )
    (net (code "195") (name "unconnected-(U$2F-PC5-Pad58)") (class "Default")
      (node (ref "U$2") (pin "58") (pinfunction "PC5_58") (pintype "bidirectional"))
    )
    (net (code "196") (name "unconnected-(U$2G-BOOT0-Pad197)") (class "Default")
      (node (ref "U$2") (pin "197") (pinfunction "BOOT0_197") (pintype "bidirectional"))
    )
    (net (code "197") (name "unconnected-(U$2G-PA13-Pad147)") (class "Default")
      (node (ref "U$2") (pin "147") (pinfunction "PA13_147") (pintype "bidirectional"))
    )
    (net (code "198") (name "unconnected-(U$2G-PA14-Pad159)") (class "Default")
      (node (ref "U$2") (pin "159") (pinfunction "PA14_159") (pintype "bidirectional"))
    )
    (net (code "199") (name "unconnected-(U$2G-PD5-Pad169)") (class "Default")
      (node (ref "U$2") (pin "169") (pinfunction "PD5_169") (pintype "bidirectional"))
    )
    (net (code "200") (name "unconnected-(U$2G-PD6-Pad172)") (class "Default")
      (node (ref "U$2") (pin "172") (pinfunction "PD6_172") (pintype "bidirectional"))
    )
    (net (code "201") (name "unconnected-(U$2G-PDR_ON-Pad203)") (class "Default")
      (node (ref "U$2") (pin "203") (pinfunction "PDR_ON_203") (pintype "bidirectional"))
    )
    (net (code "202") (name "unconnected-(U$2G-PH0-Pad32)") (class "Default")
      (node (ref "U$2") (pin "32") (pinfunction "PH0_32") (pintype "bidirectional"))
    )
    (net (code "203") (name "unconnected-(U$2G-PH1-Pad33)") (class "Default")
      (node (ref "U$2") (pin "33") (pinfunction "PH1_33") (pintype "bidirectional"))
    )
    (net (code "204") (name "unconnected-(U$2G-VBAT-Pad6)") (class "Default")
      (node (ref "U$2") (pin "6") (pinfunction "VBAT_6") (pintype "bidirectional"))
    )
    (net (code "205") (name "unconnected-(U$2G-VCAP1-Pad92)") (class "Default")
      (node (ref "U$2") (pin "92") (pinfunction "VCAP1_92") (pintype "bidirectional"))
    )
    (net (code "206") (name "unconnected-(U$2G-VCAP2-Pad148)") (class "Default")
      (node (ref "U$2") (pin "148") (pinfunction "VCAP2_148") (pintype "bidirectional"))
    )
    (net (code "207") (name "unconnected-(U$2G-VDD-Pad15)") (class "Default")
      (node (ref "U$2") (pin "15") (pinfunction "VDD_15") (pintype "bidirectional"))
    )
    (net (code "208") (name "unconnected-(U$2G-VDD-Pad26)") (class "Default")
      (node (ref "U$2") (pin "26") (pinfunction "VDD_26") (pintype "bidirectional"))
    )
    (net (code "209") (name "unconnected-(U$2G-VDD-Pad39)") (class "Default")
      (node (ref "U$2") (pin "39") (pinfunction "VDD_39") (pintype "bidirectional"))
    )
    (net (code "210") (name "unconnected-(U$2G-VDD-Pad52)") (class "Default")
      (node (ref "U$2") (pin "52") (pinfunction "VDD_52") (pintype "bidirectional"))
    )
    (net (code "211") (name "unconnected-(U$2G-VDD-Pad59)") (class "Default")
      (node (ref "U$2") (pin "59") (pinfunction "VDD_59") (pintype "bidirectional"))
    )
    (net (code "212") (name "unconnected-(U$2G-VDD-Pad73)") (class "Default")
      (node (ref "U$2") (pin "73") (pinfunction "VDD_73") (pintype "bidirectional"))
    )
    (net (code "213") (name "unconnected-(U$2G-VDD-Pad83)") (class "Default")
      (node (ref "U$2") (pin "83") (pinfunction "VDD_83") (pintype "bidirectional"))
    )
    (net (code "214") (name "unconnected-(U$2G-VDD-Pad94)") (class "Default")
      (node (ref "U$2") (pin "94") (pinfunction "VDD_94") (pintype "bidirectional"))
    )
    (net (code "215") (name "unconnected-(U$2G-VDD-Pad103)") (class "Default")
      (node (ref "U$2") (pin "103") (pinfunction "VDD_103") (pintype "bidirectional"))
    )
    (net (code "216") (name "unconnected-(U$2G-VDD-Pad115)") (class "Default")
      (node (ref "U$2") (pin "115") (pinfunction "VDD_115") (pintype "bidirectional"))
    )
    (net (code "217") (name "unconnected-(U$2G-VDD-Pad124)") (class "Default")
      (node (ref "U$2") (pin "124") (pinfunction "VDD_124") (pintype "bidirectional"))
    )
    (net (code "218") (name "unconnected-(U$2G-VDD-Pad150)") (class "Default")
      (node (ref "U$2") (pin "150") (pinfunction "VDD_150") (pintype "bidirectional"))
    )
    (net (code "219") (name "unconnected-(U$2G-VDD-Pad158)") (class "Default")
      (node (ref "U$2") (pin "158") (pinfunction "VDD_158") (pintype "bidirectional"))
    )
    (net (code "220") (name "unconnected-(U$2G-VDD-Pad171)") (class "Default")
      (node (ref "U$2") (pin "171") (pinfunction "VDD_171") (pintype "bidirectional"))
    )
    (net (code "221") (name "unconnected-(U$2G-VDD-Pad185)") (class "Default")
      (node (ref "U$2") (pin "185") (pinfunction "VDD_185") (pintype "bidirectional"))
    )
    (net (code "222") (name "unconnected-(U$2G-VDD-Pad204)") (class "Default")
      (node (ref "U$2") (pin "204") (pinfunction "VDD_204") (pintype "bidirectional"))
    )
    (net (code "223") (name "unconnected-(U$2G-VDDA-Pad42)") (class "Default")
      (node (ref "U$2") (pin "42") (pinfunction "VDDA_42") (pintype "bidirectional"))
    )
    (net (code "224") (name "unconnected-(U$2G-VDDUSB-Pad137)") (class "Default")
      (node (ref "U$2") (pin "137") (pinfunction "VDDUSB_137") (pintype "bidirectional"))
    )
    (net (code "225") (name "unconnected-(U$2G-VREF+-Pad41)") (class "Default")
      (node (ref "U$2") (pin "41") (pinfunction "VREF+_41") (pintype "bidirectional"))
    )
    (net (code "226") (name "unconnected-(U$2G-VSS-Pad14)") (class "Default")
      (node (ref "U$2") (pin "14") (pinfunction "VSS_14") (pintype "bidirectional"))
    )
    (net (code "227") (name "unconnected-(U$2G-VSS-Pad25)") (class "Default")
      (node (ref "U$2") (pin "25") (pinfunction "VSS_25") (pintype "bidirectional"))
    )
    (net (code "228") (name "unconnected-(U$2G-VSS-Pad51)") (class "Default")
      (node (ref "U$2") (pin "51") (pinfunction "VSS_51") (pintype "bidirectional"))
    )
    (net (code "229") (name "unconnected-(U$2G-VSS-Pad60)") (class "Default")
      (node (ref "U$2") (pin "60") (pinfunction "VSS_60") (pintype "bidirectional"))
    )
    (net (code "230") (name "unconnected-(U$2G-VSS-Pad72)") (class "Default")
      (node (ref "U$2") (pin "72") (pinfunction "VSS_72") (pintype "bidirectional"))
    )
    (net (code "231") (name "unconnected-(U$2G-VSS-Pad82)") (class "Default")
      (node (ref "U$2") (pin "82") (pinfunction "VSS_82") (pintype "bidirectional"))
    )
    (net (code "232") (name "unconnected-(U$2G-VSS-Pad93)") (class "Default")
      (node (ref "U$2") (pin "93") (pinfunction "VSS_93") (pintype "bidirectional"))
    )
    (net (code "233") (name "unconnected-(U$2G-VSS-Pad114)") (class "Default")
      (node (ref "U$2") (pin "114") (pinfunction "VSS_114") (pintype "bidirectional"))
    )
    (net (code "234") (name "unconnected-(U$2G-VSS-Pad125)") (class "Default")
      (node (ref "U$2") (pin "125") (pinfunction "VSS_125") (pintype "bidirectional"))
    )
    (net (code "235") (name "unconnected-(U$2G-VSS-Pad136)") (class "Default")
      (node (ref "U$2") (pin "136") (pinfunction "VSS_136") (pintype "bidirectional"))
    )
    (net (code "236") (name "unconnected-(U$2G-VSS-Pad149)") (class "Default")
      (node (ref "U$2") (pin "149") (pinfunction "VSS_149") (pintype "bidirectional"))
    )
    (net (code "237") (name "unconnected-(U$2G-VSS-Pad170)") (class "Default")
      (node (ref "U$2") (pin "170") (pinfunction "VSS_170") (pintype "bidirectional"))
    )
    (net (code "238") (name "unconnected-(U$2G-VSS-Pad184)") (class "Default")
      (node (ref "U$2") (pin "184") (pinfunction "VSS_184") (pintype "bidirectional"))
    )
    (net (code "239") (name "unconnected-(U$2G-VSS-Pad202)") (class "Default")
      (node (ref "U$2") (pin "202") (pinfunction "VSS_202") (pintype "bidirectional"))
    )
    (net (code "240") (name "unconnected-(U$2G-VSSA-Pad40)") (class "Default")
      (node (ref "U$2") (pin "40") (pinfunction "VSSA_40") (pintype "bidirectional"))
    )
    (net (code "241") (name "unconnected-(U$2G-~{RST}-Pad34)") (class "Default")
      (node (ref "U$2") (pin "34") (pinfunction "~{RST}_34") (pintype "bidirectional"))
    )
    (net (code "242") (name "unconnected-(U$2H-PC8-Pad140)") (class "Default")
      (node (ref "U$2") (pin "140") (pinfunction "PC8_140") (pintype "bidirectional"))
    )
    (net (code "243") (name "unconnected-(U$2H-PC9-Pad141)") (class "Default")
      (node (ref "U$2") (pin "141") (pinfunction "PC9_141") (pintype "bidirectional"))
    )
    (net (code "244") (name "unconnected-(U$2H-PC10-Pad161)") (class "Default")
      (node (ref "U$2") (pin "161") (pinfunction "PC10_161") (pintype "bidirectional"))
    )
    (net (code "245") (name "unconnected-(U$2H-PC11-Pad162)") (class "Default")
      (node (ref "U$2") (pin "162") (pinfunction "PC11_162") (pintype "bidirectional"))
    )
    (net (code "246") (name "unconnected-(U$2H-PC12-Pad163)") (class "Default")
      (node (ref "U$2") (pin "163") (pinfunction "PC12_163") (pintype "bidirectional"))
    )
    (net (code "247") (name "unconnected-(U$2H-PC13-Pad8)") (class "Default")
      (node (ref "U$2") (pin "8") (pinfunction "PC13_8") (pintype "bidirectional"))
    )
    (net (code "248") (name "unconnected-(U$2H-PD2-Pad166)") (class "Default")
      (node (ref "U$2") (pin "166") (pinfunction "PD2_166") (pintype "bidirectional"))
    )
    (net (code "249") (name "unconnected-(U$2I-PC0-Pad35)") (class "Default")
      (node (ref "U$2") (pin "35") (pinfunction "PC0_35") (pintype "bidirectional"))
    )
    (net (code "250") (name "unconnected-(U$2I-PD0-Pad164)") (class "Default")
      (node (ref "U$2") (pin "164") (pinfunction "PD0_164") (pintype "bidirectional"))
    )
    (net (code "251") (name "unconnected-(U$2I-PD1-Pad165)") (class "Default")
      (node (ref "U$2") (pin "165") (pinfunction "PD1_165") (pintype "bidirectional"))
    )
    (net (code "252") (name "unconnected-(U$2I-PD8-Pad108)") (class "Default")
      (node (ref "U$2") (pin "108") (pinfunction "PD8_108") (pintype "bidirectional"))
    )
    (net (code "253") (name "unconnected-(U$2I-PD9-Pad109)") (class "Default")
      (node (ref "U$2") (pin "109") (pinfunction "PD9_109") (pintype "bidirectional"))
    )
    (net (code "254") (name "unconnected-(U$2I-PD10-Pad110)") (class "Default")
      (node (ref "U$2") (pin "110") (pinfunction "PD10_110") (pintype "bidirectional"))
    )
    (net (code "255") (name "unconnected-(U$2I-PD14-Pad116)") (class "Default")
      (node (ref "U$2") (pin "116") (pinfunction "PD14_116") (pintype "bidirectional"))
    )
    (net (code "256") (name "unconnected-(U$2I-PD15-Pad117)") (class "Default")
      (node (ref "U$2") (pin "117") (pinfunction "PD15_117") (pintype "bidirectional"))
    )
    (net (code "257") (name "unconnected-(U$2I-PE0-Pad200)") (class "Default")
      (node (ref "U$2") (pin "200") (pinfunction "PE0_200") (pintype "bidirectional"))
    )
    (net (code "258") (name "unconnected-(U$2I-PE1-Pad201)") (class "Default")
      (node (ref "U$2") (pin "201") (pinfunction "PE1_201") (pintype "bidirectional"))
    )
    (net (code "259") (name "unconnected-(U$2I-PE7-Pad79)") (class "Default")
      (node (ref "U$2") (pin "79") (pinfunction "PE7_79") (pintype "bidirectional"))
    )
    (net (code "260") (name "unconnected-(U$2I-PE8-Pad80)") (class "Default")
      (node (ref "U$2") (pin "80") (pinfunction "PE8_80") (pintype "bidirectional"))
    )
    (net (code "261") (name "unconnected-(U$2I-PE9-Pad81)") (class "Default")
      (node (ref "U$2") (pin "81") (pinfunction "PE9_81") (pintype "bidirectional"))
    )
    (net (code "262") (name "unconnected-(U$2I-PE10-Pad84)") (class "Default")
      (node (ref "U$2") (pin "84") (pinfunction "PE10_84") (pintype "bidirectional"))
    )
    (net (code "263") (name "unconnected-(U$2I-PE11-Pad85)") (class "Default")
      (node (ref "U$2") (pin "85") (pinfunction "PE11_85") (pintype "bidirectional"))
    )
    (net (code "264") (name "unconnected-(U$2I-PE12-Pad86)") (class "Default")
      (node (ref "U$2") (pin "86") (pinfunction "PE12_86") (pintype "bidirectional"))
    )
    (net (code "265") (name "unconnected-(U$2I-PE13-Pad87)") (class "Default")
      (node (ref "U$2") (pin "87") (pinfunction "PE13_87") (pintype "bidirectional"))
    )
    (net (code "266") (name "unconnected-(U$2I-PE14-Pad88)") (class "Default")
      (node (ref "U$2") (pin "88") (pinfunction "PE14_88") (pintype "bidirectional"))
    )
    (net (code "267") (name "unconnected-(U$2I-PE15-Pad89)") (class "Default")
      (node (ref "U$2") (pin "89") (pinfunction "PE15_89") (pintype "bidirectional"))
    )
    (net (code "268") (name "unconnected-(U$2I-PF0-Pad16)") (class "Default")
      (node (ref "U$2") (pin "16") (pinfunction "PF0_16") (pintype "bidirectional"))
    )
    (net (code "269") (name "unconnected-(U$2I-PF1-Pad17)") (class "Default")
      (node (ref "U$2") (pin "17") (pinfunction "PF1_17") (pintype "bidirectional"))
    )
    (net (code "270") (name "unconnected-(U$2I-PF2-Pad18)") (class "Default")
      (node (ref "U$2") (pin "18") (pinfunction "PF2_18") (pintype "bidirectional"))
    )
    (net (code "271") (name "unconnected-(U$2I-PF3-Pad22)") (class "Default")
      (node (ref "U$2") (pin "22") (pinfunction "PF3_22") (pintype "bidirectional"))
    )
    (net (code "272") (name "unconnected-(U$2I-PF4-Pad23)") (class "Default")
      (node (ref "U$2") (pin "23") (pinfunction "PF4_23") (pintype "bidirectional"))
    )
    (net (code "273") (name "unconnected-(U$2I-PF5-Pad24)") (class "Default")
      (node (ref "U$2") (pin "24") (pinfunction "PF5_24") (pintype "bidirectional"))
    )
    (net (code "274") (name "unconnected-(U$2I-PF11-Pad70)") (class "Default")
      (node (ref "U$2") (pin "70") (pinfunction "PF11_70") (pintype "bidirectional"))
    )
    (net (code "275") (name "unconnected-(U$2I-PF12-Pad71)") (class "Default")
      (node (ref "U$2") (pin "71") (pinfunction "PF12_71") (pintype "bidirectional"))
    )
    (net (code "276") (name "unconnected-(U$2I-PF13-Pad74)") (class "Default")
      (node (ref "U$2") (pin "74") (pinfunction "PF13_74") (pintype "bidirectional"))
    )
    (net (code "277") (name "unconnected-(U$2I-PF14-Pad75)") (class "Default")
      (node (ref "U$2") (pin "75") (pinfunction "PF14_75") (pintype "bidirectional"))
    )
    (net (code "278") (name "unconnected-(U$2I-PF15-Pad76)") (class "Default")
      (node (ref "U$2") (pin "76") (pinfunction "PF15_76") (pintype "bidirectional"))
    )
    (net (code "279") (name "unconnected-(U$2I-PG0-Pad77)") (class "Default")
      (node (ref "U$2") (pin "77") (pinfunction "PG0_77") (pintype "bidirectional"))
    )
    (net (code "280") (name "unconnected-(U$2I-PG1-Pad78)") (class "Default")
      (node (ref "U$2") (pin "78") (pinfunction "PG1_78") (pintype "bidirectional"))
    )
    (net (code "281") (name "unconnected-(U$2I-PG2-Pad129)") (class "Default")
      (node (ref "U$2") (pin "129") (pinfunction "PG2_129") (pintype "bidirectional"))
    )
    (net (code "282") (name "unconnected-(U$2I-PG4-Pad131)") (class "Default")
      (node (ref "U$2") (pin "131") (pinfunction "PG4_131") (pintype "bidirectional"))
    )
    (net (code "283") (name "unconnected-(U$2I-PG5-Pad132)") (class "Default")
      (node (ref "U$2") (pin "132") (pinfunction "PG5_132") (pintype "bidirectional"))
    )
    (net (code "284") (name "unconnected-(U$2I-PG8-Pad135)") (class "Default")
      (node (ref "U$2") (pin "135") (pinfunction "PG8_135") (pintype "bidirectional"))
    )
    (net (code "285") (name "unconnected-(U$2I-PG15-Pad191)") (class "Default")
      (node (ref "U$2") (pin "191") (pinfunction "PG15_191") (pintype "bidirectional"))
    )
    (net (code "286") (name "unconnected-(U$2I-PH8-Pad98)") (class "Default")
      (node (ref "U$2") (pin "98") (pinfunction "PH8_98") (pintype "bidirectional"))
    )
    (net (code "287") (name "unconnected-(U$2I-PH9-Pad99)") (class "Default")
      (node (ref "U$2") (pin "99") (pinfunction "PH9_99") (pintype "bidirectional"))
    )
    (net (code "288") (name "unconnected-(U$2I-PH10-Pad100)") (class "Default")
      (node (ref "U$2") (pin "100") (pinfunction "PH10_100") (pintype "bidirectional"))
    )
    (net (code "289") (name "unconnected-(U$2I-PH11-Pad101)") (class "Default")
      (node (ref "U$2") (pin "101") (pinfunction "PH11_101") (pintype "bidirectional"))
    )
    (net (code "290") (name "unconnected-(U$2I-PH12-Pad102)") (class "Default")
      (node (ref "U$2") (pin "102") (pinfunction "PH12_102") (pintype "bidirectional"))
    )
    (net (code "291") (name "unconnected-(U$2I-PH13-Pad151)") (class "Default")
      (node (ref "U$2") (pin "151") (pinfunction "PH13_151") (pintype "bidirectional"))
    )
    (net (code "292") (name "unconnected-(U$2I-PH14-Pad152)") (class "Default")
      (node (ref "U$2") (pin "152") (pinfunction "PH14_152") (pintype "bidirectional"))
    )
    (net (code "293") (name "unconnected-(U$2I-PH15-Pad153)") (class "Default")
      (node (ref "U$2") (pin "153") (pinfunction "PH15_153") (pintype "bidirectional"))
    )
    (net (code "294") (name "unconnected-(U$2I-PI0-Pad154)") (class "Default")
      (node (ref "U$2") (pin "154") (pinfunction "PI0_154") (pintype "bidirectional"))
    )
    (net (code "295") (name "unconnected-(U$2I-PI1-Pad155)") (class "Default")
      (node (ref "U$2") (pin "155") (pinfunction "PI1_155") (pintype "bidirectional"))
    )
    (net (code "296") (name "unconnected-(U$2I-PI2-Pad156)") (class "Default")
      (node (ref "U$2") (pin "156") (pinfunction "PI2_156") (pintype "bidirectional"))
    )
    (net (code "297") (name "unconnected-(U$2I-PI3-Pad157)") (class "Default")
      (node (ref "U$2") (pin "157") (pinfunction "PI3_157") (pintype "bidirectional"))
    )
    (net (code "298") (name "unconnected-(U$2I-PI4-Pad205)") (class "Default")
      (node (ref "U$2") (pin "205") (pinfunction "PI4_205") (pintype "bidirectional"))
    )
    (net (code "299") (name "unconnected-(U$2I-PI5-Pad206)") (class "Default")
      (node (ref "U$2") (pin "206") (pinfunction "PI5_206") (pintype "bidirectional"))
    )
    (net (code "300") (name "unconnected-(U$2I-PI6-Pad207)") (class "Default")
      (node (ref "U$2") (pin "207") (pinfunction "PI6_207") (pintype "bidirectional"))
    )
    (net (code "301") (name "unconnected-(U$2I-PI7-Pad208)") (class "Default")
      (node (ref "U$2") (pin "208") (pinfunction "PI7_208") (pintype "bidirectional"))
    )
    (net (code "302") (name "unconnected-(U$2I-PI9-Pad11)") (class "Default")
      (node (ref "U$2") (pin "11") (pinfunction "PI9_11") (pintype "bidirectional"))
    )
    (net (code "303") (name "unconnected-(U$2I-PI10-Pad12)") (class "Default")
      (node (ref "U$2") (pin "12") (pinfunction "PI10_12") (pintype "bidirectional"))
    )
    (net (code "304") (name "unconnected-(U$2J-PA3-Pad50)") (class "Default")
      (node (ref "U$2") (pin "50") (pinfunction "PA3_50") (pintype "bidirectional"))
    )
    (net (code "305") (name "unconnected-(U$2J-PB2-Pad63)") (class "Default")
      (node (ref "U$2") (pin "63") (pinfunction "PB2_63") (pintype "bidirectional"))
    )
    (net (code "306") (name "unconnected-(U$2J-PB6-Pad195)") (class "Default")
      (node (ref "U$2") (pin "195") (pinfunction "PB6_195") (pintype "bidirectional"))
    )
    (net (code "307") (name "unconnected-(U$2J-PB7-Pad196)") (class "Default")
      (node (ref "U$2") (pin "196") (pinfunction "PB7_196") (pintype "bidirectional"))
    )
    (net (code "308") (name "unconnected-(U$2J-PB8-Pad198)") (class "Default")
      (node (ref "U$2") (pin "198") (pinfunction "PB8_198") (pintype "bidirectional"))
    )
    (net (code "309") (name "unconnected-(U$2J-PB14-Pad106)") (class "Default")
      (node (ref "U$2") (pin "106") (pinfunction "PB14_106") (pintype "bidirectional"))
    )
    (net (code "310") (name "unconnected-(U$2J-PC2_C-Pad37)") (class "Default")
      (node (ref "U$2") (pin "37") (pinfunction "PC2_C_37") (pintype "bidirectional"))
    )
    (net (code "311") (name "unconnected-(U$2J-PC3_C-Pad38)") (class "Default")
      (node (ref "U$2") (pin "38") (pinfunction "PC3_C_38") (pintype "bidirectional"))
    )
    (net (code "312") (name "unconnected-(U$2J-PC6-Pad138)") (class "Default")
      (node (ref "U$2") (pin "138") (pinfunction "PC6_138") (pintype "bidirectional"))
    )
    (net (code "313") (name "unconnected-(U$2J-PC7-Pad139)") (class "Default")
      (node (ref "U$2") (pin "139") (pinfunction "PC7_139") (pintype "bidirectional"))
    )
    (net (code "314") (name "unconnected-(U$2J-PC14-Pad9)") (class "Default")
      (node (ref "U$2") (pin "9") (pinfunction "PC14_9") (pintype "bidirectional"))
    )
    (net (code "315") (name "unconnected-(U$2J-PC15-Pad10)") (class "Default")
      (node (ref "U$2") (pin "10") (pinfunction "PC15_10") (pintype "bidirectional"))
    )
    (net (code "316") (name "unconnected-(U$2J-PD3-Pad167)") (class "Default")
      (node (ref "U$2") (pin "167") (pinfunction "PD3_167") (pintype "bidirectional"))
    )
    (net (code "317") (name "unconnected-(U$2J-PD4-Pad168)") (class "Default")
      (node (ref "U$2") (pin "168") (pinfunction "PD4_168") (pintype "bidirectional"))
    )
    (net (code "318") (name "unconnected-(U$2J-PD7-Pad173)") (class "Default")
      (node (ref "U$2") (pin "173") (pinfunction "PD7_173") (pintype "bidirectional"))
    )
    (net (code "319") (name "unconnected-(U$2J-PE3-Pad2)") (class "Default")
      (node (ref "U$2") (pin "2") (pinfunction "PE3_2") (pintype "bidirectional"))
    )
    (net (code "320") (name "unconnected-(U$2J-PH5-Pad49)") (class "Default")
      (node (ref "U$2") (pin "49") (pinfunction "PH5_49") (pintype "bidirectional"))
    )
    (net (code "321") (name "unconnected-(U$2J-PH6-Pad96)") (class "Default")
      (node (ref "U$2") (pin "96") (pinfunction "PH6_96") (pintype "bidirectional"))
    )
    (net (code "322") (name "unconnected-(U$2J-PH7-Pad97)") (class "Default")
      (node (ref "U$2") (pin "97") (pinfunction "PH7_97") (pintype "bidirectional"))
    )
    (net (code "323") (name "unconnected-(U$2K-PA5-Pad54)") (class "Default")
      (node (ref "U$2") (pin "54") (pinfunction "PA5_54") (pintype "bidirectional"))
    )
    (net (code "324") (name "unconnected-(U$2K-PA6-Pad55)") (class "Default")
      (node (ref "U$2") (pin "55") (pinfunction "PA6_55") (pintype "bidirectional"))
    )
    (net (code "325") (name "unconnected-(U$2K-PA8-Pad142)") (class "Default")
      (node (ref "U$2") (pin "142") (pinfunction "PA8_142") (pintype "bidirectional"))
    )
    (net (code "326") (name "unconnected-(U$2K-PA9-Pad143)") (class "Default")
      (node (ref "U$2") (pin "143") (pinfunction "PA9_143") (pintype "bidirectional"))
    )
    (net (code "327") (name "unconnected-(U$2K-PA10-Pad144)") (class "Default")
      (node (ref "U$2") (pin "144") (pinfunction "PA10_144") (pintype "bidirectional"))
    )
    (net (code "328") (name "unconnected-(U$2K-PA11-Pad145)") (class "Default")
      (node (ref "U$2") (pin "145") (pinfunction "PA11_145") (pintype "bidirectional"))
    )
    (net (code "329") (name "unconnected-(U$2K-PA12-Pad146)") (class "Default")
      (node (ref "U$2") (pin "146") (pinfunction "PA12_146") (pintype "bidirectional"))
    )
    (net (code "330") (name "unconnected-(U$2L-PA0-Pad43)") (class "Default")
      (node (ref "U$2") (pin "43") (pinfunction "PA0_43") (pintype "bidirectional"))
    )
    (net (code "331") (name "unconnected-(U$2L-PA15-Pad160)") (class "Default")
      (node (ref "U$2") (pin "160") (pinfunction "PA15_160") (pintype "bidirectional"))
    )
    (net (code "332") (name "unconnected-(U$2L-PI12-Pad19)") (class "Default")
      (node (ref "U$2") (pin "19") (pinfunction "PI12_19") (pintype "bidirectional"))
    )
    (net (code "333") (name "unconnected-(U$2L-PI13-Pad20)") (class "Default")
      (node (ref "U$2") (pin "20") (pinfunction "PI13_20") (pintype "bidirectional"))
    )
    (net (code "334") (name "unconnected-(U$2L-PI14-Pad21)") (class "Default")
      (node (ref "U$2") (pin "21") (pinfunction "PI14_21") (pintype "bidirectional"))
    )
    (net (code "335") (name "unconnected-(U$2L-PI15-Pad64)") (class "Default")
      (node (ref "U$2") (pin "64") (pinfunction "PI15_64") (pintype "bidirectional"))
    )
    (net (code "336") (name "unconnected-(U$2L-PJ0-Pad65)") (class "Default")
      (node (ref "U$2") (pin "65") (pinfunction "PJ0_65") (pintype "bidirectional"))
    )
    (net (code "337") (name "unconnected-(U$2L-PJ1-Pad66)") (class "Default")
      (node (ref "U$2") (pin "66") (pinfunction "PJ1_66") (pintype "bidirectional"))
    )
    (net (code "338") (name "unconnected-(U$2L-PJ2-Pad67)") (class "Default")
      (node (ref "U$2") (pin "67") (pinfunction "PJ2_67") (pintype "bidirectional"))
    )
    (net (code "339") (name "unconnected-(U$2L-PJ3-Pad68)") (class "Default")
      (node (ref "U$2") (pin "68") (pinfunction "PJ3_68") (pintype "bidirectional"))
    )
    (net (code "340") (name "unconnected-(U$2L-PJ4-Pad69)") (class "Default")
      (node (ref "U$2") (pin "69") (pinfunction "PJ4_69") (pintype "bidirectional"))
    )
    (net (code "341") (name "unconnected-(U$2L-PJ5-Pad95)") (class "Default")
      (node (ref "U$2") (pin "95") (pinfunction "PJ5_95") (pintype "bidirectional"))
    )
    (net (code "342") (name "unconnected-(U$2L-PJ6-Pad118)") (class "Default")
      (node (ref "U$2") (pin "118") (pinfunction "PJ6_118") (pintype "bidirectional"))
    )
    (net (code "343") (name "unconnected-(U$2L-PJ7-Pad119)") (class "Default")
      (node (ref "U$2") (pin "119") (pinfunction "PJ7_119") (pintype "bidirectional"))
    )
    (net (code "344") (name "unconnected-(U$2L-PJ8-Pad120)") (class "Default")
      (node (ref "U$2") (pin "120") (pinfunction "PJ8_120") (pintype "bidirectional"))
    )
    (net (code "345") (name "unconnected-(U$2L-PJ9-Pad121)") (class "Default")
      (node (ref "U$2") (pin "121") (pinfunction "PJ9_121") (pintype "bidirectional"))
    )
    (net (code "346") (name "unconnected-(U$2L-PJ10-Pad122)") (class "Default")
      (node (ref "U$2") (pin "122") (pinfunction "PJ10_122") (pintype "bidirectional"))
    )
    (net (code "347") (name "unconnected-(U$2L-PJ11-Pad123)") (class "Default")
      (node (ref "U$2") (pin "123") (pinfunction "PJ11_123") (pintype "bidirectional"))
    )
    (net (code "348") (name "unconnected-(U$2L-PJ12-Pad174)") (class "Default")
      (node (ref "U$2") (pin "174") (pinfunction "PJ12_174") (pintype "bidirectional"))
    )
    (net (code "349") (name "unconnected-(U$2L-PJ13-Pad175)") (class "Default")
      (node (ref "U$2") (pin "175") (pinfunction "PJ13_175") (pintype "bidirectional"))
    )
    (net (code "350") (name "unconnected-(U$2L-PJ14-Pad176)") (class "Default")
      (node (ref "U$2") (pin "176") (pinfunction "PJ14_176") (pintype "bidirectional"))
    )
    (net (code "351") (name "unconnected-(U$2L-PJ15-Pad177)") (class "Default")
      (node (ref "U$2") (pin "177") (pinfunction "PJ15_177") (pintype "bidirectional"))
    )
    (net (code "352") (name "unconnected-(U$2L-PK0-Pad126)") (class "Default")
      (node (ref "U$2") (pin "126") (pinfunction "PK0_126") (pintype "bidirectional"))
    )
    (net (code "353") (name "unconnected-(U$2L-PK1-Pad127)") (class "Default")
      (node (ref "U$2") (pin "127") (pinfunction "PK1_127") (pintype "bidirectional"))
    )
    (net (code "354") (name "unconnected-(U$2L-PK2-Pad128)") (class "Default")
      (node (ref "U$2") (pin "128") (pinfunction "PK2_128") (pintype "bidirectional"))
    )
    (net (code "355") (name "unconnected-(U$2L-PK3-Pad186)") (class "Default")
      (node (ref "U$2") (pin "186") (pinfunction "PK3_186") (pintype "bidirectional"))
    )
    (net (code "356") (name "unconnected-(U$2L-PK4-Pad187)") (class "Default")
      (node (ref "U$2") (pin "187") (pinfunction "PK4_187") (pintype "bidirectional"))
    )
    (net (code "357") (name "unconnected-(U$2L-PK5-Pad188)") (class "Default")
      (node (ref "U$2") (pin "188") (pinfunction "PK5_188") (pintype "bidirectional"))
    )
    (net (code "358") (name "unconnected-(U$2L-PK6-Pad189)") (class "Default")
      (node (ref "U$2") (pin "189") (pinfunction "PK6_189") (pintype "bidirectional"))
    )
    (net (code "359") (name "unconnected-(U$2L-PK7-Pad190)") (class "Default")
      (node (ref "U$2") (pin "190") (pinfunction "PK7_190") (pintype "bidirectional"))
    )
    (net (code "360") (name "unconnected-(U$2M-PA4-Pad53)") (class "Default")
      (node (ref "U$2") (pin "53") (pinfunction "PA4_53") (pintype "bidirectional"))
    )
    (net (code "361") (name "unconnected-(U$2M-PB3-Pad192)") (class "Default")
      (node (ref "U$2") (pin "192") (pinfunction "PB3_192") (pintype "bidirectional"))
    )
    (net (code "362") (name "unconnected-(U$2M-PB4-Pad193)") (class "Default")
      (node (ref "U$2") (pin "193") (pinfunction "PB4_193") (pintype "bidirectional"))
    )
    (net (code "363") (name "unconnected-(U$2M-PB5-Pad194)") (class "Default")
      (node (ref "U$2") (pin "194") (pinfunction "PB5_194") (pintype "bidirectional"))
    )
    (net (code "364") (name "unconnected-(U$2M-PE2-Pad1)") (class "Default")
      (node (ref "U$2") (pin "1") (pinfunction "PE2_1") (pintype "bidirectional"))
    )
    (net (code "365") (name "unconnected-(U$2M-PE4-Pad3)") (class "Default")
      (node (ref "U$2") (pin "3") (pinfunction "PE4_3") (pintype "bidirectional"))
    )
    (net (code "366") (name "unconnected-(U$2M-PE5-Pad4)") (class "Default")
      (node (ref "U$2") (pin "4") (pinfunction "PE5_4") (pintype "bidirectional"))
    )
    (net (code "367") (name "unconnected-(U$2M-PE6-Pad5)") (class "Default")
      (node (ref "U$2") (pin "5") (pinfunction "PE6_5") (pintype "bidirectional"))
    )
    (net (code "368") (name "unconnected-(U$2M-PF6-Pad27)") (class "Default")
      (node (ref "U$2") (pin "27") (pinfunction "PF6_27") (pintype "bidirectional"))
    )
    (net (code "369") (name "unconnected-(U$2M-PF7-Pad28)") (class "Default")
      (node (ref "U$2") (pin "28") (pinfunction "PF7_28") (pintype "bidirectional"))
    )
    (net (code "370") (name "unconnected-(U$2M-PF8-Pad29)") (class "Default")
      (node (ref "U$2") (pin "29") (pinfunction "PF8_29") (pintype "bidirectional"))
    )
    (net (code "371") (name "unconnected-(U$2M-PF9-Pad30)") (class "Default")
      (node (ref "U$2") (pin "30") (pinfunction "PF9_30") (pintype "bidirectional"))
    )
    (net (code "372") (name "unconnected-(U$2M-PI8-Pad7)") (class "Default")
      (node (ref "U$2") (pin "7") (pinfunction "PI8_7") (pintype "bidirectional"))
    )
    (net (code "373") (name "unconnected-(U$2M-PI11-Pad13)") (class "Default")
      (node (ref "U$2") (pin "13") (pinfunction "PI11_13") (pintype "bidirectional"))
    )
    (net (code "374") (name "unconnected-(U1-A0-Pad23)") (class "Default")
      (node (ref "U1") (pin "23") (pinfunction "A0_23") (pintype "bidirectional"))
    )
    (net (code "375") (name "unconnected-(U1-A1-Pad24)") (class "Default")
      (node (ref "U1") (pin "24") (pinfunction "A1_24") (pintype "bidirectional"))
    )
    (net (code "376") (name "unconnected-(U1-A2-Pad25)") (class "Default")
      (node (ref "U1") (pin "25") (pinfunction "A2_25") (pintype "bidirectional"))
    )
    (net (code "377") (name "unconnected-(U1-A3-Pad26)") (class "Default")
      (node (ref "U1") (pin "26") (pinfunction "A3_26") (pintype "bidirectional"))
    )
    (net (code "378") (name "unconnected-(U1-A4-Pad29)") (class "Default")
      (node (ref "U1") (pin "29") (pinfunction "A4_29") (pintype "bidirectional"))
    )
    (net (code "379") (name "unconnected-(U1-A5-Pad30)") (class "Default")
      (node (ref "U1") (pin "30") (pinfunction "A5_30") (pintype "bidirectional"))
    )
    (net (code "380") (name "unconnected-(U1-A6-Pad31)") (class "Default")
      (node (ref "U1") (pin "31") (pinfunction "A6_31") (pintype "bidirectional"))
    )
    (net (code "381") (name "unconnected-(U1-A7-Pad32)") (class "Default")
      (node (ref "U1") (pin "32") (pinfunction "A7_32") (pintype "bidirectional"))
    )
    (net (code "382") (name "unconnected-(U1-A8-Pad33)") (class "Default")
      (node (ref "U1") (pin "33") (pinfunction "A8_33") (pintype "bidirectional"))
    )
    (net (code "383") (name "unconnected-(U1-A9-Pad34)") (class "Default")
      (node (ref "U1") (pin "34") (pinfunction "A9_34") (pintype "bidirectional"))
    )
    (net (code "384") (name "unconnected-(U1-A10-Pad22)") (class "Default")
      (node (ref "U1") (pin "22") (pinfunction "A10_22") (pintype "bidirectional"))
    )
    (net (code "385") (name "unconnected-(U1-A11-Pad35)") (class "Default")
      (node (ref "U1") (pin "35") (pinfunction "A11_35") (pintype "bidirectional"))
    )
    (net (code "386") (name "unconnected-(U1-BA0-Pad20)") (class "Default")
      (node (ref "U1") (pin "20") (pinfunction "BA0_20") (pintype "bidirectional"))
    )
    (net (code "387") (name "unconnected-(U1-BA1-Pad21)") (class "Default")
      (node (ref "U1") (pin "21") (pinfunction "BA1_21") (pintype "bidirectional"))
    )
    (net (code "388") (name "unconnected-(U1-CAS-Pad17)") (class "Default")
      (node (ref "U1") (pin "17") (pinfunction "CAS_17") (pintype "bidirectional"))
    )
    (net (code "389") (name "unconnected-(U1-CKE-Pad37)") (class "Default")
      (node (ref "U1") (pin "37") (pinfunction "CKE_37") (pintype "bidirectional"))
    )
    (net (code "390") (name "unconnected-(U1-CLK-Pad38)") (class "Default")
      (node (ref "U1") (pin "38") (pinfunction "CLK_38") (pintype "bidirectional"))
    )
    (net (code "391") (name "unconnected-(U1-CS-Pad19)") (class "Default")
      (node (ref "U1") (pin "19") (pinfunction "CS_19") (pintype "bidirectional"))
    )
    (net (code "392") (name "unconnected-(U1-DQ0-Pad2)") (class "Default")
      (node (ref "U1") (pin "2") (pinfunction "DQ0_2") (pintype "bidirectional"))
    )
    (net (code "393") (name "unconnected-(U1-DQ1-Pad4)") (class "Default")
      (node (ref "U1") (pin "4") (pinfunction "DQ1_4") (pintype "bidirectional"))
    )
    (net (code "394") (name "unconnected-(U1-DQ2-Pad5)") (class "Default")
      (node (ref "U1") (pin "5") (pinfunction "DQ2_5") (pintype "bidirectional"))
    )
    (net (code "395") (name "unconnected-(U1-DQ3-Pad7)") (class "Default")
      (node (ref "U1") (pin "7") (pinfunction "DQ3_7") (pintype "bidirectional"))
    )
    (net (code "396") (name "unconnected-(U1-DQ4-Pad8)") (class "Default")
      (node (ref "U1") (pin "8") (pinfunction "DQ4_8") (pintype "bidirectional"))
    )
    (net (code "397") (name "unconnected-(U1-DQ5-Pad10)") (class "Default")
      (node (ref "U1") (pin "10") (pinfunction "DQ5_10") (pintype "bidirectional"))
    )
    (net (code "398") (name "unconnected-(U1-DQ6-Pad11)") (class "Default")
      (node (ref "U1") (pin "11") (pinfunction "DQ6_11") (pintype "bidirectional"))
    )
    (net (code "399") (name "unconnected-(U1-DQ7-Pad13)") (class "Default")
      (node (ref "U1") (pin "13") (pinfunction "DQ7_13") (pintype "bidirectional"))
    )
    (net (code "400") (name "unconnected-(U1-DQ8-Pad42)") (class "Default")
      (node (ref "U1") (pin "42") (pinfunction "DQ8_42") (pintype "bidirectional"))
    )
    (net (code "401") (name "unconnected-(U1-DQ9-Pad44)") (class "Default")
      (node (ref "U1") (pin "44") (pinfunction "DQ9_44") (pintype "bidirectional"))
    )
    (net (code "402") (name "unconnected-(U1-DQ10-Pad45)") (class "Default")
      (node (ref "U1") (pin "45") (pinfunction "DQ10_45") (pintype "bidirectional"))
    )
    (net (code "403") (name "unconnected-(U1-DQ11-Pad47)") (class "Default")
      (node (ref "U1") (pin "47") (pinfunction "DQ11_47") (pintype "bidirectional"))
    )
    (net (code "404") (name "unconnected-(U1-DQ12-Pad48)") (class "Default")
      (node (ref "U1") (pin "48") (pinfunction "DQ12_48") (pintype "bidirectional"))
    )
    (net (code "405") (name "unconnected-(U1-DQ13-Pad50)") (class "Default")
      (node (ref "U1") (pin "50") (pinfunction "DQ13_50") (pintype "bidirectional"))
    )
    (net (code "406") (name "unconnected-(U1-DQ14-Pad51)") (class "Default")
      (node (ref "U1") (pin "51") (pinfunction "DQ14_51") (pintype "bidirectional"))
    )
    (net (code "407") (name "unconnected-(U1-DQ15-Pad53)") (class "Default")
      (node (ref "U1") (pin "53") (pinfunction "DQ15_53") (pintype "bidirectional"))
    )
    (net (code "408") (name "unconnected-(U1-DQMH-Pad39)") (class "Default")
      (node (ref "U1") (pin "39") (pinfunction "DQMH_39") (pintype "bidirectional"))
    )
    (net (code "409") (name "unconnected-(U1-DQML-Pad15)") (class "Default")
      (node (ref "U1") (pin "15") (pinfunction "DQML_15") (pintype "bidirectional"))
    )
    (net (code "410") (name "unconnected-(U1-NC1-Pad36)") (class "Default")
      (node (ref "U1") (pin "36") (pinfunction "NC1_36") (pintype "bidirectional"))
    )
    (net (code "411") (name "unconnected-(U1-NC2-Pad40)") (class "Default")
      (node (ref "U1") (pin "40") (pinfunction "NC2_40") (pintype "bidirectional"))
    )
    (net (code "412") (name "unconnected-(U1-RAS-Pad18)") (class "Default")
      (node (ref "U1") (pin "18") (pinfunction "RAS_18") (pintype "bidirectional"))
    )
    (net (code "413") (name "unconnected-(U1-VDD1-Pad1)") (class "Default")
      (node (ref "U1") (pin "1") (pinfunction "VDD1_1") (pintype "bidirectional"))
    )
    (net (code "414") (name "unconnected-(U1-VDD2-Pad14)") (class "Default")
      (node (ref "U1") (pin "14") (pinfunction "VDD2_14") (pintype "bidirectional"))
    )
    (net (code "415") (name "unconnected-(U1-VDD3-Pad27)") (class "Default")
      (node (ref "U1") (pin "27") (pinfunction "VDD3_27") (pintype "bidirectional"))
    )
    (net (code "416") (name "unconnected-(U1-VDDQ1-Pad3)") (class "Default")
      (node (ref "U1") (pin "3") (pinfunction "VDDQ1_3") (pintype "bidirectional"))
    )
    (net (code "417") (name "unconnected-(U1-VDDQ2-Pad9)") (class "Default")
      (node (ref "U1") (pin "9") (pinfunction "VDDQ2_9") (pintype "bidirectional"))
    )
    (net (code "418") (name "unconnected-(U1-VDDQ3-Pad43)") (class "Default")
      (node (ref "U1") (pin "43") (pinfunction "VDDQ3_43") (pintype "bidirectional"))
    )
    (net (code "419") (name "unconnected-(U1-VDDQ4-Pad49)") (class "Default")
      (node (ref "U1") (pin "49") (pinfunction "VDDQ4_49") (pintype "bidirectional"))
    )
    (net (code "420") (name "unconnected-(U1-VSS1-Pad28)") (class "Default")
      (node (ref "U1") (pin "28") (pinfunction "VSS1_28") (pintype "bidirectional"))
    )
    (net (code "421") (name "unconnected-(U1-VSS2-Pad41)") (class "Default")
      (node (ref "U1") (pin "41") (pinfunction "VSS2_41") (pintype "bidirectional"))
    )
    (net (code "422") (name "unconnected-(U1-VSS3-Pad54)") (class "Default")
      (node (ref "U1") (pin "54") (pinfunction "VSS3_54") (pintype "bidirectional"))
    )
    (net (code "423") (name "unconnected-(U1-VSSQ1-Pad6)") (class "Default")
      (node (ref "U1") (pin "6") (pinfunction "VSSQ1_6") (pintype "bidirectional"))
    )
    (net (code "424") (name "unconnected-(U1-VSSQ2-Pad12)") (class "Default")
      (node (ref "U1") (pin "12") (pinfunction "VSSQ2_12") (pintype "bidirectional"))
    )
    (net (code "425") (name "unconnected-(U1-VSSQ3-Pad46)") (class "Default")
      (node (ref "U1") (pin "46") (pinfunction "VSSQ3_46") (pintype "bidirectional"))
    )
    (net (code "426") (name "unconnected-(U1-VSSQ4-Pad52)") (class "Default")
      (node (ref "U1") (pin "52") (pinfunction "VSSQ4_52") (pintype "bidirectional"))
    )
    (net (code "427") (name "unconnected-(U1-WE-Pad16)") (class "Default")
      (node (ref "U1") (pin "16") (pinfunction "WE_16") (pintype "bidirectional"))
    )
    (net (code "428") (name "~{CCTL}") (class "Default")
      (node (ref "U$1") (pin "30") (pinfunction "~{CCTL}_30") (pintype "bidirectional"))
      (node (ref "U$3") (pin "PA18") (pinfunction "A18_PA18") (pintype "bidirectional"))
    )
    (net (code "429") (name "~{EXTSEL}") (class "Default")
      (node (ref "U$1") (pin "26") (pinfunction "~{EXT}_26") (pintype "bidirectional"))
      (node (ref "U$3") (pin "PB13") (pinfunction "B13_PB13") (pintype "bidirectional"))
    )
    (net (code "430") (name "~{HALT}") (class "Default")
      (node (ref "U$1") (pin "33") (pinfunction "~{HLT}_33") (pintype "bidirectional"))
      (node (ref "U$3") (pin "PA14") (pinfunction "A14_PA14") (pintype "bidirectional"))
    )
    (net (code "431") (name "~{IRQ}") (class "Default")
      (node (ref "U$1") (pin "23") (pinfunction "~{IRQ}_23") (pintype "bidirectional"))
      (node (ref "U$3") (pin "PB14") (pinfunction "B14_PB14") (pintype "bidirectional"))
    )
    (net (code "432") (name "~{MPD}") (class "Default")
      (node (ref "U$1") (pin "25") (pinfunction "~{MPD}_25") (pintype "bidirectional"))
      (node (ref "U$3") (pin "PA15") (pinfunction "A15_PA15") (pintype "bidirectional"))
    )
    (net (code "433") (name "~{RST}") (class "Default")
      (node (ref "U$1") (pin "31") (pinfunction "~{RST}_31") (pintype "bidirectional"))
      (node (ref "U$3") (pin "PA17") (pinfunction "A17_PA17") (pintype "bidirectional"))
    )
    (net (code "434") (name "~{S4}") (class "Default")
      (node (ref "U$1") (pin "37") (pinfunction "~{S4}_37") (pintype "bidirectional"))
      (node (ref "U$3") (pin "PB16") (pinfunction "B16_PB16") (pintype "bidirectional"))
    )
    (net (code "435") (name "~{S5}") (class "Default")
      (node (ref "U$1") (pin "39") (pinfunction "~{S5}_39") (pintype "bidirectional"))
      (node (ref "U$3") (pin "PB18") (pinfunction "B18_PB18") (pintype "bidirectional"))
    )
    (net (code "436") (name "~{SP1_IRQ}") (class "Default")
      (node (ref "R4") (pin "2") (pinfunction "2_2") (pintype "passive"))
      (node (ref "SLOT1") (pin "B10") (pinfunction "B10_B10") (pintype "bidirectional"))
    )
    (net (code "437") (name "~{SPI0_IRQ}") (class "Default")
      (node (ref "R5") (pin "2") (pinfunction "2_2") (pintype "passive"))
      (node (ref "SLOT0") (pin "B10") (pinfunction "B10_B10") (pintype "bidirectional"))
    )
    (net (code "438") (name "~{SPI2_IRQ}") (class "Default")
      (node (ref "R3") (pin "2") (pinfunction "2_2") (pintype "passive"))
      (node (ref "SLOT2") (pin "B10") (pinfunction "B10_B10") (pintype "bidirectional"))
    )
    (net (code "439") (name "~{SPI3_IRQ}") (class "Default")
      (node (ref "R2") (pin "2") (pinfunction "2_2") (pintype "passive"))
      (node (ref "SLOT3") (pin "B10") (pinfunction "B10_B10") (pintype "bidirectional"))
    )
    (net (code "440") (name "~{SPI4_IRQ}") (class "Default")
      (node (ref "R1") (pin "2") (pinfunction "2_2") (pintype "passive"))
      (node (ref "SLOT4") (pin "B10") (pinfunction "B10_B10") (pintype "bidirectional"))
    )
  )
)
